# BloopPadMaxx_01.net
KiCad netlist of a schematic drawn in Altium Designer
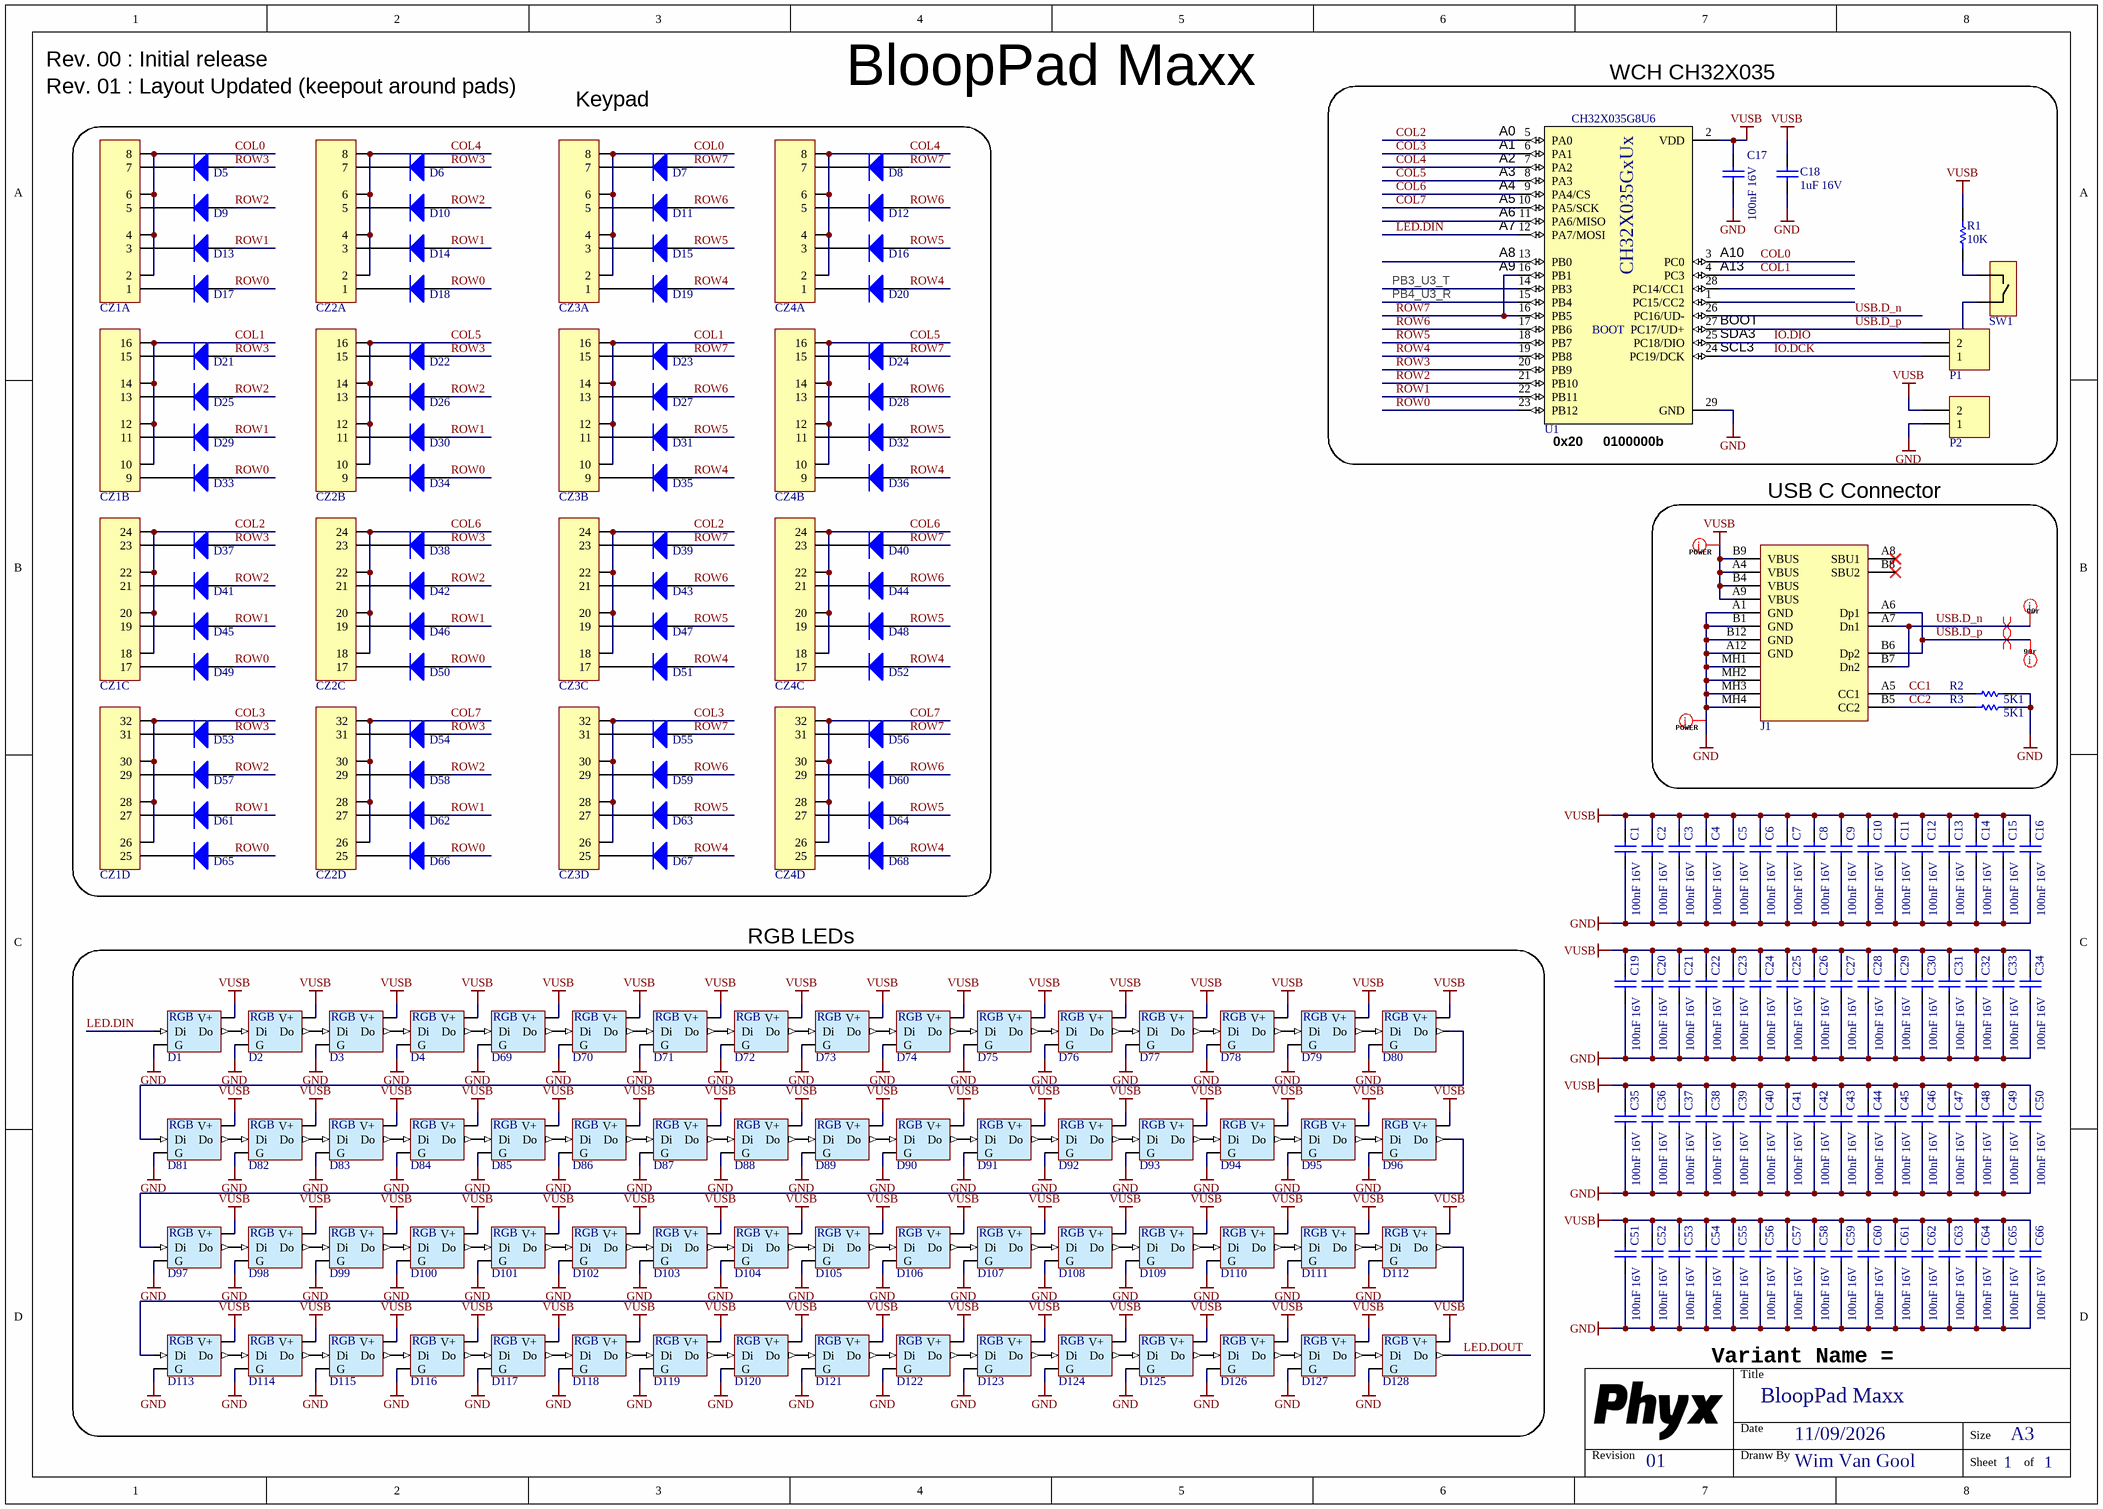
[diagram p0: BloopPadMaxx_01.SchDoc]

(export (version "E")
  (design (tool "Eeschema 10.0.6"))
  (components
    (comp (ref "C1")
      (value "100nF 16V")
      (footprint "C0603_N")
      (description "Capacitor Ceramic")
      (fields (field (name "Comment") "CAP_CERAMIC"))
      (libsource (lib "Phyx_Components") (part "CAP_CERAMIC"))
    )
    (comp (ref "C2")
      (value "100nF 16V")
      (footprint "C0603_N")
      (description "Capacitor Ceramic")
      (fields (field (name "Comment") "CAP_CERAMIC"))
      (libsource (lib "Phyx_Components") (part "CAP_CERAMIC"))
    )
    (comp (ref "C3")
      (value "100nF 16V")
      (footprint "C0603_N")
      (description "Capacitor Ceramic")
      (fields (field (name "Comment") "CAP_CERAMIC"))
      (libsource (lib "Phyx_Components") (part "CAP_CERAMIC"))
    )
    (comp (ref "C4")
      (value "100nF 16V")
      (footprint "C0603_N")
      (description "Capacitor Ceramic")
      (fields (field (name "Comment") "CAP_CERAMIC"))
      (libsource (lib "Phyx_Components") (part "CAP_CERAMIC"))
    )
    (comp (ref "C5")
      (value "100nF 16V")
      (footprint "C0603_N")
      (description "Capacitor Ceramic")
      (fields (field (name "Comment") "CAP_CERAMIC"))
      (libsource (lib "Phyx_Components") (part "CAP_CERAMIC"))
    )
    (comp (ref "C6")
      (value "100nF 16V")
      (footprint "C0603_N")
      (description "Capacitor Ceramic")
      (fields (field (name "Comment") "CAP_CERAMIC"))
      (libsource (lib "Phyx_Components") (part "CAP_CERAMIC"))
    )
    (comp (ref "C7")
      (value "100nF 16V")
      (footprint "C0603_N")
      (description "Capacitor Ceramic")
      (fields (field (name "Comment") "CAP_CERAMIC"))
      (libsource (lib "Phyx_Components") (part "CAP_CERAMIC"))
    )
    (comp (ref "C8")
      (value "100nF 16V")
      (footprint "C0603_N")
      (description "Capacitor Ceramic")
      (fields (field (name "Comment") "CAP_CERAMIC"))
      (libsource (lib "Phyx_Components") (part "CAP_CERAMIC"))
    )
    (comp (ref "C9")
      (value "100nF 16V")
      (footprint "C0603_N")
      (description "Capacitor Ceramic")
      (fields (field (name "Comment") "CAP_CERAMIC"))
      (libsource (lib "Phyx_Components") (part "CAP_CERAMIC"))
    )
    (comp (ref "C10")
      (value "100nF 16V")
      (footprint "C0603_N")
      (description "Capacitor Ceramic")
      (fields (field (name "Comment") "CAP_CERAMIC"))
      (libsource (lib "Phyx_Components") (part "CAP_CERAMIC"))
    )
    (comp (ref "C11")
      (value "100nF 16V")
      (footprint "C0603_N")
      (description "Capacitor Ceramic")
      (fields (field (name "Comment") "CAP_CERAMIC"))
      (libsource (lib "Phyx_Components") (part "CAP_CERAMIC"))
    )
    (comp (ref "C12")
      (value "100nF 16V")
      (footprint "C0603_N")
      (description "Capacitor Ceramic")
      (fields (field (name "Comment") "CAP_CERAMIC"))
      (libsource (lib "Phyx_Components") (part "CAP_CERAMIC"))
    )
    (comp (ref "C13")
      (value "100nF 16V")
      (footprint "C0603_N")
      (description "Capacitor Ceramic")
      (fields (field (name "Comment") "CAP_CERAMIC"))
      (libsource (lib "Phyx_Components") (part "CAP_CERAMIC"))
    )
    (comp (ref "C14")
      (value "100nF 16V")
      (footprint "C0603_N")
      (description "Capacitor Ceramic")
      (fields (field (name "Comment") "CAP_CERAMIC"))
      (libsource (lib "Phyx_Components") (part "CAP_CERAMIC"))
    )
    (comp (ref "C15")
      (value "100nF 16V")
      (footprint "C0603_N")
      (description "Capacitor Ceramic")
      (fields (field (name "Comment") "CAP_CERAMIC"))
      (libsource (lib "Phyx_Components") (part "CAP_CERAMIC"))
    )
    (comp (ref "C16")
      (value "100nF 16V")
      (footprint "C0603_N")
      (description "Capacitor Ceramic")
      (fields (field (name "Comment") "CAP_CERAMIC"))
      (libsource (lib "Phyx_Components") (part "CAP_CERAMIC"))
    )
    (comp (ref "C17")
      (value "100nF 16V")
      (footprint "C0603_N")
      (description "Capacitor Ceramic")
      (libsource (lib "Phyx_Components") (part "CAP_CERAMIC"))
    )
    (comp (ref "C18")
      (value "1uF 16V")
      (footprint "C0603_N")
      (description "Capacitor Ceramic")
      (libsource (lib "Phyx_Components") (part "CAP_CERAMIC"))
    )
    (comp (ref "C19")
      (value "100nF 16V")
      (footprint "C0603_N")
      (description "Capacitor Ceramic")
      (fields (field (name "Comment") "CAP_CERAMIC"))
      (libsource (lib "Phyx_Components") (part "CAP_CERAMIC"))
    )
    (comp (ref "C20")
      (value "100nF 16V")
      (footprint "C0603_N")
      (description "Capacitor Ceramic")
      (fields (field (name "Comment") "CAP_CERAMIC"))
      (libsource (lib "Phyx_Components") (part "CAP_CERAMIC"))
    )
    (comp (ref "C21")
      (value "100nF 16V")
      (footprint "C0603_N")
      (description "Capacitor Ceramic")
      (fields (field (name "Comment") "CAP_CERAMIC"))
      (libsource (lib "Phyx_Components") (part "CAP_CERAMIC"))
    )
    (comp (ref "C22")
      (value "100nF 16V")
      (footprint "C0603_N")
      (description "Capacitor Ceramic")
      (fields (field (name "Comment") "CAP_CERAMIC"))
      (libsource (lib "Phyx_Components") (part "CAP_CERAMIC"))
    )
    (comp (ref "C23")
      (value "100nF 16V")
      (footprint "C0603_N")
      (description "Capacitor Ceramic")
      (fields (field (name "Comment") "CAP_CERAMIC"))
      (libsource (lib "Phyx_Components") (part "CAP_CERAMIC"))
    )
    (comp (ref "C24")
      (value "100nF 16V")
      (footprint "C0603_N")
      (description "Capacitor Ceramic")
      (fields (field (name "Comment") "CAP_CERAMIC"))
      (libsource (lib "Phyx_Components") (part "CAP_CERAMIC"))
    )
    (comp (ref "C25")
      (value "100nF 16V")
      (footprint "C0603_N")
      (description "Capacitor Ceramic")
      (fields (field (name "Comment") "CAP_CERAMIC"))
      (libsource (lib "Phyx_Components") (part "CAP_CERAMIC"))
    )
    (comp (ref "C26")
      (value "100nF 16V")
      (footprint "C0603_N")
      (description "Capacitor Ceramic")
      (fields (field (name "Comment") "CAP_CERAMIC"))
      (libsource (lib "Phyx_Components") (part "CAP_CERAMIC"))
    )
    (comp (ref "C27")
      (value "100nF 16V")
      (footprint "C0603_N")
      (description "Capacitor Ceramic")
      (fields (field (name "Comment") "CAP_CERAMIC"))
      (libsource (lib "Phyx_Components") (part "CAP_CERAMIC"))
    )
    (comp (ref "C28")
      (value "100nF 16V")
      (footprint "C0603_N")
      (description "Capacitor Ceramic")
      (fields (field (name "Comment") "CAP_CERAMIC"))
      (libsource (lib "Phyx_Components") (part "CAP_CERAMIC"))
    )
    (comp (ref "C29")
      (value "100nF 16V")
      (footprint "C0603_N")
      (description "Capacitor Ceramic")
      (fields (field (name "Comment") "CAP_CERAMIC"))
      (libsource (lib "Phyx_Components") (part "CAP_CERAMIC"))
    )
    (comp (ref "C30")
      (value "100nF 16V")
      (footprint "C0603_N")
      (description "Capacitor Ceramic")
      (fields (field (name "Comment") "CAP_CERAMIC"))
      (libsource (lib "Phyx_Components") (part "CAP_CERAMIC"))
    )
    (comp (ref "C31")
      (value "100nF 16V")
      (footprint "C0603_N")
      (description "Capacitor Ceramic")
      (fields (field (name "Comment") "CAP_CERAMIC"))
      (libsource (lib "Phyx_Components") (part "CAP_CERAMIC"))
    )
    (comp (ref "C32")
      (value "100nF 16V")
      (footprint "C0603_N")
      (description "Capacitor Ceramic")
      (fields (field (name "Comment") "CAP_CERAMIC"))
      (libsource (lib "Phyx_Components") (part "CAP_CERAMIC"))
    )
    (comp (ref "C33")
      (value "100nF 16V")
      (footprint "C0603_N")
      (description "Capacitor Ceramic")
      (fields (field (name "Comment") "CAP_CERAMIC"))
      (libsource (lib "Phyx_Components") (part "CAP_CERAMIC"))
    )
    (comp (ref "C34")
      (value "100nF 16V")
      (footprint "C0603_N")
      (description "Capacitor Ceramic")
      (fields (field (name "Comment") "CAP_CERAMIC"))
      (libsource (lib "Phyx_Components") (part "CAP_CERAMIC"))
    )
    (comp (ref "C35")
      (value "100nF 16V")
      (footprint "C0603_N")
      (description "Capacitor Ceramic")
      (fields (field (name "Comment") "CAP_CERAMIC"))
      (libsource (lib "Phyx_Components") (part "CAP_CERAMIC"))
    )
    (comp (ref "C36")
      (value "100nF 16V")
      (footprint "C0603_N")
      (description "Capacitor Ceramic")
      (fields (field (name "Comment") "CAP_CERAMIC"))
      (libsource (lib "Phyx_Components") (part "CAP_CERAMIC"))
    )
    (comp (ref "C37")
      (value "100nF 16V")
      (footprint "C0603_N")
      (description "Capacitor Ceramic")
      (fields (field (name "Comment") "CAP_CERAMIC"))
      (libsource (lib "Phyx_Components") (part "CAP_CERAMIC"))
    )
    (comp (ref "C38")
      (value "100nF 16V")
      (footprint "C0603_N")
      (description "Capacitor Ceramic")
      (fields (field (name "Comment") "CAP_CERAMIC"))
      (libsource (lib "Phyx_Components") (part "CAP_CERAMIC"))
    )
    (comp (ref "C39")
      (value "100nF 16V")
      (footprint "C0603_N")
      (description "Capacitor Ceramic")
      (fields (field (name "Comment") "CAP_CERAMIC"))
      (libsource (lib "Phyx_Components") (part "CAP_CERAMIC"))
    )
    (comp (ref "C40")
      (value "100nF 16V")
      (footprint "C0603_N")
      (description "Capacitor Ceramic")
      (fields (field (name "Comment") "CAP_CERAMIC"))
      (libsource (lib "Phyx_Components") (part "CAP_CERAMIC"))
    )
    (comp (ref "C41")
      (value "100nF 16V")
      (footprint "C0603_N")
      (description "Capacitor Ceramic")
      (fields (field (name "Comment") "CAP_CERAMIC"))
      (libsource (lib "Phyx_Components") (part "CAP_CERAMIC"))
    )
    (comp (ref "C42")
      (value "100nF 16V")
      (footprint "C0603_N")
      (description "Capacitor Ceramic")
      (fields (field (name "Comment") "CAP_CERAMIC"))
      (libsource (lib "Phyx_Components") (part "CAP_CERAMIC"))
    )
    (comp (ref "C43")
      (value "100nF 16V")
      (footprint "C0603_N")
      (description "Capacitor Ceramic")
      (fields (field (name "Comment") "CAP_CERAMIC"))
      (libsource (lib "Phyx_Components") (part "CAP_CERAMIC"))
    )
    (comp (ref "C44")
      (value "100nF 16V")
      (footprint "C0603_N")
      (description "Capacitor Ceramic")
      (fields (field (name "Comment") "CAP_CERAMIC"))
      (libsource (lib "Phyx_Components") (part "CAP_CERAMIC"))
    )
    (comp (ref "C45")
      (value "100nF 16V")
      (footprint "C0603_N")
      (description "Capacitor Ceramic")
      (fields (field (name "Comment") "CAP_CERAMIC"))
      (libsource (lib "Phyx_Components") (part "CAP_CERAMIC"))
    )
    (comp (ref "C46")
      (value "100nF 16V")
      (footprint "C0603_N")
      (description "Capacitor Ceramic")
      (fields (field (name "Comment") "CAP_CERAMIC"))
      (libsource (lib "Phyx_Components") (part "CAP_CERAMIC"))
    )
    (comp (ref "C47")
      (value "100nF 16V")
      (footprint "C0603_N")
      (description "Capacitor Ceramic")
      (fields (field (name "Comment") "CAP_CERAMIC"))
      (libsource (lib "Phyx_Components") (part "CAP_CERAMIC"))
    )
    (comp (ref "C48")
      (value "100nF 16V")
      (footprint "C0603_N")
      (description "Capacitor Ceramic")
      (fields (field (name "Comment") "CAP_CERAMIC"))
      (libsource (lib "Phyx_Components") (part "CAP_CERAMIC"))
    )
    (comp (ref "C49")
      (value "100nF 16V")
      (footprint "C0603_N")
      (description "Capacitor Ceramic")
      (fields (field (name "Comment") "CAP_CERAMIC"))
      (libsource (lib "Phyx_Components") (part "CAP_CERAMIC"))
    )
    (comp (ref "C50")
      (value "100nF 16V")
      (footprint "C0603_N")
      (description "Capacitor Ceramic")
      (fields (field (name "Comment") "CAP_CERAMIC"))
      (libsource (lib "Phyx_Components") (part "CAP_CERAMIC"))
    )
    (comp (ref "C51")
      (value "100nF 16V")
      (footprint "C0603_N")
      (description "Capacitor Ceramic")
      (fields (field (name "Comment") "CAP_CERAMIC"))
      (libsource (lib "Phyx_Components") (part "CAP_CERAMIC"))
    )
    (comp (ref "C52")
      (value "100nF 16V")
      (footprint "C0603_N")
      (description "Capacitor Ceramic")
      (fields (field (name "Comment") "CAP_CERAMIC"))
      (libsource (lib "Phyx_Components") (part "CAP_CERAMIC"))
    )
    (comp (ref "C53")
      (value "100nF 16V")
      (footprint "C0603_N")
      (description "Capacitor Ceramic")
      (fields (field (name "Comment") "CAP_CERAMIC"))
      (libsource (lib "Phyx_Components") (part "CAP_CERAMIC"))
    )
    (comp (ref "C54")
      (value "100nF 16V")
      (footprint "C0603_N")
      (description "Capacitor Ceramic")
      (fields (field (name "Comment") "CAP_CERAMIC"))
      (libsource (lib "Phyx_Components") (part "CAP_CERAMIC"))
    )
    (comp (ref "C55")
      (value "100nF 16V")
      (footprint "C0603_N")
      (description "Capacitor Ceramic")
      (fields (field (name "Comment") "CAP_CERAMIC"))
      (libsource (lib "Phyx_Components") (part "CAP_CERAMIC"))
    )
    (comp (ref "C56")
      (value "100nF 16V")
      (footprint "C0603_N")
      (description "Capacitor Ceramic")
      (fields (field (name "Comment") "CAP_CERAMIC"))
      (libsource (lib "Phyx_Components") (part "CAP_CERAMIC"))
    )
    (comp (ref "C57")
      (value "100nF 16V")
      (footprint "C0603_N")
      (description "Capacitor Ceramic")
      (fields (field (name "Comment") "CAP_CERAMIC"))
      (libsource (lib "Phyx_Components") (part "CAP_CERAMIC"))
    )
    (comp (ref "C58")
      (value "100nF 16V")
      (footprint "C0603_N")
      (description "Capacitor Ceramic")
      (fields (field (name "Comment") "CAP_CERAMIC"))
      (libsource (lib "Phyx_Components") (part "CAP_CERAMIC"))
    )
    (comp (ref "C59")
      (value "100nF 16V")
      (footprint "C0603_N")
      (description "Capacitor Ceramic")
      (fields (field (name "Comment") "CAP_CERAMIC"))
      (libsource (lib "Phyx_Components") (part "CAP_CERAMIC"))
    )
    (comp (ref "C60")
      (value "100nF 16V")
      (footprint "C0603_N")
      (description "Capacitor Ceramic")
      (fields (field (name "Comment") "CAP_CERAMIC"))
      (libsource (lib "Phyx_Components") (part "CAP_CERAMIC"))
    )
    (comp (ref "C61")
      (value "100nF 16V")
      (footprint "C0603_N")
      (description "Capacitor Ceramic")
      (fields (field (name "Comment") "CAP_CERAMIC"))
      (libsource (lib "Phyx_Components") (part "CAP_CERAMIC"))
    )
    (comp (ref "C62")
      (value "100nF 16V")
      (footprint "C0603_N")
      (description "Capacitor Ceramic")
      (fields (field (name "Comment") "CAP_CERAMIC"))
      (libsource (lib "Phyx_Components") (part "CAP_CERAMIC"))
    )
    (comp (ref "C63")
      (value "100nF 16V")
      (footprint "C0603_N")
      (description "Capacitor Ceramic")
      (fields (field (name "Comment") "CAP_CERAMIC"))
      (libsource (lib "Phyx_Components") (part "CAP_CERAMIC"))
    )
    (comp (ref "C64")
      (value "100nF 16V")
      (footprint "C0603_N")
      (description "Capacitor Ceramic")
      (fields (field (name "Comment") "CAP_CERAMIC"))
      (libsource (lib "Phyx_Components") (part "CAP_CERAMIC"))
    )
    (comp (ref "C65")
      (value "100nF 16V")
      (footprint "C0603_N")
      (description "Capacitor Ceramic")
      (fields (field (name "Comment") "CAP_CERAMIC"))
      (libsource (lib "Phyx_Components") (part "CAP_CERAMIC"))
    )
    (comp (ref "C66")
      (value "100nF 16V")
      (footprint "C0603_N")
      (description "Capacitor Ceramic")
      (fields (field (name "Comment") "CAP_CERAMIC"))
      (libsource (lib "Phyx_Components") (part "CAP_CERAMIC"))
    )
    (comp (ref "CZ1")
      (value "Campzone 2020 4x4 silicone keypad")
      (footprint "CZ20_4x4")
      (libsource (lib "Phyx_Components") (part "CZ20_4x4"))
    )
    (comp (ref "CZ2")
      (value "Campzone 2020 4x4 silicone keypad")
      (footprint "CZ20_4x4")
      (libsource (lib "Phyx_Components") (part "CZ20_4x4"))
    )
    (comp (ref "CZ3")
      (value "Campzone 2020 4x4 silicone keypad")
      (footprint "CZ20_4x4")
      (libsource (lib "Phyx_Components") (part "CZ20_4x4"))
    )
    (comp (ref "CZ4")
      (value "Campzone 2020 4x4 silicone keypad")
      (footprint "CZ20_4x4")
      (libsource (lib "Phyx_Components") (part "CZ20_4x4"))
    )
    (comp (ref "D1")
      (value "WS2812 based digital RGB LED 2022 package")
      (footprint "LED_2022_WS2812B")
      (description "=Description")
      (libsource (lib "Phyx_Components") (part "LED_RGB_WS2812B_2022"))
    )
    (comp (ref "D2")
      (value "WS2812 based digital RGB LED 2022 package")
      (footprint "LED_2022_WS2812B")
      (description "=Description")
      (libsource (lib "Phyx_Components") (part "LED_RGB_WS2812B_2022"))
    )
    (comp (ref "D3")
      (value "WS2812 based digital RGB LED 2022 package")
      (footprint "LED_2022_WS2812B")
      (description "=Description")
      (libsource (lib "Phyx_Components") (part "LED_RGB_WS2812B_2022"))
    )
    (comp (ref "D4")
      (value "WS2812 based digital RGB LED 2022 package")
      (footprint "LED_2022_WS2812B")
      (description "=Description")
      (libsource (lib "Phyx_Components") (part "LED_RGB_WS2812B_2022"))
    )
    (comp (ref "D5")
      (value "1N4148W 75V 200mA 1.25Vf@150mA")
      (footprint "SOD-323_AC")
      (description "Default Diode")
      (libsource (lib "Phyx_Components") (part "DIODE_AC"))
    )
    (comp (ref "D6")
      (value "1N4148W 75V 200mA 1.25Vf@150mA")
      (footprint "SOD-323_AC")
      (description "Default Diode")
      (libsource (lib "Phyx_Components") (part "DIODE_AC"))
    )
    (comp (ref "D7")
      (value "1N4148W 75V 200mA 1.25Vf@150mA")
      (footprint "SOD-323_AC")
      (description "Default Diode")
      (libsource (lib "Phyx_Components") (part "DIODE_AC"))
    )
    (comp (ref "D8")
      (value "1N4148W 75V 200mA 1.25Vf@150mA")
      (footprint "SOD-323_AC")
      (description "Default Diode")
      (libsource (lib "Phyx_Components") (part "DIODE_AC"))
    )
    (comp (ref "D9")
      (value "1N4148W 75V 200mA 1.25Vf@150mA")
      (footprint "SOD-323_AC")
      (description "Default Diode")
      (libsource (lib "Phyx_Components") (part "DIODE_AC"))
    )
    (comp (ref "D10")
      (value "1N4148W 75V 200mA 1.25Vf@150mA")
      (footprint "SOD-323_AC")
      (description "Default Diode")
      (libsource (lib "Phyx_Components") (part "DIODE_AC"))
    )
    (comp (ref "D11")
      (value "1N4148W 75V 200mA 1.25Vf@150mA")
      (footprint "SOD-323_AC")
      (description "Default Diode")
      (libsource (lib "Phyx_Components") (part "DIODE_AC"))
    )
    (comp (ref "D12")
      (value "1N4148W 75V 200mA 1.25Vf@150mA")
      (footprint "SOD-323_AC")
      (description "Default Diode")
      (libsource (lib "Phyx_Components") (part "DIODE_AC"))
    )
    (comp (ref "D13")
      (value "1N4148W 75V 200mA 1.25Vf@150mA")
      (footprint "SOD-323_AC")
      (description "Default Diode")
      (libsource (lib "Phyx_Components") (part "DIODE_AC"))
    )
    (comp (ref "D14")
      (value "1N4148W 75V 200mA 1.25Vf@150mA")
      (footprint "SOD-323_AC")
      (description "Default Diode")
      (libsource (lib "Phyx_Components") (part "DIODE_AC"))
    )
    (comp (ref "D15")
      (value "1N4148W 75V 200mA 1.25Vf@150mA")
      (footprint "SOD-323_AC")
      (description "Default Diode")
      (libsource (lib "Phyx_Components") (part "DIODE_AC"))
    )
    (comp (ref "D16")
      (value "1N4148W 75V 200mA 1.25Vf@150mA")
      (footprint "SOD-323_AC")
      (description "Default Diode")
      (libsource (lib "Phyx_Components") (part "DIODE_AC"))
    )
    (comp (ref "D17")
      (value "1N4148W 75V 200mA 1.25Vf@150mA")
      (footprint "SOD-323_AC")
      (description "Default Diode")
      (libsource (lib "Phyx_Components") (part "DIODE_AC"))
    )
    (comp (ref "D18")
      (value "1N4148W 75V 200mA 1.25Vf@150mA")
      (footprint "SOD-323_AC")
      (description "Default Diode")
      (libsource (lib "Phyx_Components") (part "DIODE_AC"))
    )
    (comp (ref "D19")
      (value "1N4148W 75V 200mA 1.25Vf@150mA")
      (footprint "SOD-323_AC")
      (description "Default Diode")
      (libsource (lib "Phyx_Components") (part "DIODE_AC"))
    )
    (comp (ref "D20")
      (value "1N4148W 75V 200mA 1.25Vf@150mA")
      (footprint "SOD-323_AC")
      (description "Default Diode")
      (libsource (lib "Phyx_Components") (part "DIODE_AC"))
    )
    (comp (ref "D21")
      (value "1N4148W 75V 200mA 1.25Vf@150mA")
      (footprint "SOD-323_AC")
      (description "Default Diode")
      (libsource (lib "Phyx_Components") (part "DIODE_AC"))
    )
    (comp (ref "D22")
      (value "1N4148W 75V 200mA 1.25Vf@150mA")
      (footprint "SOD-323_AC")
      (description "Default Diode")
      (libsource (lib "Phyx_Components") (part "DIODE_AC"))
    )
    (comp (ref "D23")
      (value "1N4148W 75V 200mA 1.25Vf@150mA")
      (footprint "SOD-323_AC")
      (description "Default Diode")
      (libsource (lib "Phyx_Components") (part "DIODE_AC"))
    )
    (comp (ref "D24")
      (value "1N4148W 75V 200mA 1.25Vf@150mA")
      (footprint "SOD-323_AC")
      (description "Default Diode")
      (libsource (lib "Phyx_Components") (part "DIODE_AC"))
    )
    (comp (ref "D25")
      (value "1N4148W 75V 200mA 1.25Vf@150mA")
      (footprint "SOD-323_AC")
      (description "Default Diode")
      (libsource (lib "Phyx_Components") (part "DIODE_AC"))
    )
    (comp (ref "D26")
      (value "1N4148W 75V 200mA 1.25Vf@150mA")
      (footprint "SOD-323_AC")
      (description "Default Diode")
      (libsource (lib "Phyx_Components") (part "DIODE_AC"))
    )
    (comp (ref "D27")
      (value "1N4148W 75V 200mA 1.25Vf@150mA")
      (footprint "SOD-323_AC")
      (description "Default Diode")
      (libsource (lib "Phyx_Components") (part "DIODE_AC"))
    )
    (comp (ref "D28")
      (value "1N4148W 75V 200mA 1.25Vf@150mA")
      (footprint "SOD-323_AC")
      (description "Default Diode")
      (libsource (lib "Phyx_Components") (part "DIODE_AC"))
    )
    (comp (ref "D29")
      (value "1N4148W 75V 200mA 1.25Vf@150mA")
      (footprint "SOD-323_AC")
      (description "Default Diode")
      (libsource (lib "Phyx_Components") (part "DIODE_AC"))
    )
    (comp (ref "D30")
      (value "1N4148W 75V 200mA 1.25Vf@150mA")
      (footprint "SOD-323_AC")
      (description "Default Diode")
      (libsource (lib "Phyx_Components") (part "DIODE_AC"))
    )
    (comp (ref "D31")
      (value "1N4148W 75V 200mA 1.25Vf@150mA")
      (footprint "SOD-323_AC")
      (description "Default Diode")
      (libsource (lib "Phyx_Components") (part "DIODE_AC"))
    )
    (comp (ref "D32")
      (value "1N4148W 75V 200mA 1.25Vf@150mA")
      (footprint "SOD-323_AC")
      (description "Default Diode")
      (libsource (lib "Phyx_Components") (part "DIODE_AC"))
    )
    (comp (ref "D33")
      (value "1N4148W 75V 200mA 1.25Vf@150mA")
      (footprint "SOD-323_AC")
      (description "Default Diode")
      (libsource (lib "Phyx_Components") (part "DIODE_AC"))
    )
    (comp (ref "D34")
      (value "1N4148W 75V 200mA 1.25Vf@150mA")
      (footprint "SOD-323_AC")
      (description "Default Diode")
      (libsource (lib "Phyx_Components") (part "DIODE_AC"))
    )
    (comp (ref "D35")
      (value "1N4148W 75V 200mA 1.25Vf@150mA")
      (footprint "SOD-323_AC")
      (description "Default Diode")
      (libsource (lib "Phyx_Components") (part "DIODE_AC"))
    )
    (comp (ref "D36")
      (value "1N4148W 75V 200mA 1.25Vf@150mA")
      (footprint "SOD-323_AC")
      (description "Default Diode")
      (libsource (lib "Phyx_Components") (part "DIODE_AC"))
    )
    (comp (ref "D37")
      (value "1N4148W 75V 200mA 1.25Vf@150mA")
      (footprint "SOD-323_AC")
      (description "Default Diode")
      (libsource (lib "Phyx_Components") (part "DIODE_AC"))
    )
    (comp (ref "D38")
      (value "1N4148W 75V 200mA 1.25Vf@150mA")
      (footprint "SOD-323_AC")
      (description "Default Diode")
      (libsource (lib "Phyx_Components") (part "DIODE_AC"))
    )
    (comp (ref "D39")
      (value "1N4148W 75V 200mA 1.25Vf@150mA")
      (footprint "SOD-323_AC")
      (description "Default Diode")
      (libsource (lib "Phyx_Components") (part "DIODE_AC"))
    )
    (comp (ref "D40")
      (value "1N4148W 75V 200mA 1.25Vf@150mA")
      (footprint "SOD-323_AC")
      (description "Default Diode")
      (libsource (lib "Phyx_Components") (part "DIODE_AC"))
    )
    (comp (ref "D41")
      (value "1N4148W 75V 200mA 1.25Vf@150mA")
      (footprint "SOD-323_AC")
      (description "Default Diode")
      (libsource (lib "Phyx_Components") (part "DIODE_AC"))
    )
    (comp (ref "D42")
      (value "1N4148W 75V 200mA 1.25Vf@150mA")
      (footprint "SOD-323_AC")
      (description "Default Diode")
      (libsource (lib "Phyx_Components") (part "DIODE_AC"))
    )
    (comp (ref "D43")
      (value "1N4148W 75V 200mA 1.25Vf@150mA")
      (footprint "SOD-323_AC")
      (description "Default Diode")
      (libsource (lib "Phyx_Components") (part "DIODE_AC"))
    )
    (comp (ref "D44")
      (value "1N4148W 75V 200mA 1.25Vf@150mA")
      (footprint "SOD-323_AC")
      (description "Default Diode")
      (libsource (lib "Phyx_Components") (part "DIODE_AC"))
    )
    (comp (ref "D45")
      (value "1N4148W 75V 200mA 1.25Vf@150mA")
      (footprint "SOD-323_AC")
      (description "Default Diode")
      (libsource (lib "Phyx_Components") (part "DIODE_AC"))
    )
    (comp (ref "D46")
      (value "1N4148W 75V 200mA 1.25Vf@150mA")
      (footprint "SOD-323_AC")
      (description "Default Diode")
      (libsource (lib "Phyx_Components") (part "DIODE_AC"))
    )
    (comp (ref "D47")
      (value "1N4148W 75V 200mA 1.25Vf@150mA")
      (footprint "SOD-323_AC")
      (description "Default Diode")
      (libsource (lib "Phyx_Components") (part "DIODE_AC"))
    )
    (comp (ref "D48")
      (value "1N4148W 75V 200mA 1.25Vf@150mA")
      (footprint "SOD-323_AC")
      (description "Default Diode")
      (libsource (lib "Phyx_Components") (part "DIODE_AC"))
    )
    (comp (ref "D49")
      (value "1N4148W 75V 200mA 1.25Vf@150mA")
      (footprint "SOD-323_AC")
      (description "Default Diode")
      (libsource (lib "Phyx_Components") (part "DIODE_AC"))
    )
    (comp (ref "D50")
      (value "1N4148W 75V 200mA 1.25Vf@150mA")
      (footprint "SOD-323_AC")
      (description "Default Diode")
      (libsource (lib "Phyx_Components") (part "DIODE_AC"))
    )
    (comp (ref "D51")
      (value "1N4148W 75V 200mA 1.25Vf@150mA")
      (footprint "SOD-323_AC")
      (description "Default Diode")
      (libsource (lib "Phyx_Components") (part "DIODE_AC"))
    )
    (comp (ref "D52")
      (value "1N4148W 75V 200mA 1.25Vf@150mA")
      (footprint "SOD-323_AC")
      (description "Default Diode")
      (libsource (lib "Phyx_Components") (part "DIODE_AC"))
    )
    (comp (ref "D53")
      (value "1N4148W 75V 200mA 1.25Vf@150mA")
      (footprint "SOD-323_AC")
      (description "Default Diode")
      (libsource (lib "Phyx_Components") (part "DIODE_AC"))
    )
    (comp (ref "D54")
      (value "1N4148W 75V 200mA 1.25Vf@150mA")
      (footprint "SOD-323_AC")
      (description "Default Diode")
      (libsource (lib "Phyx_Components") (part "DIODE_AC"))
    )
    (comp (ref "D55")
      (value "1N4148W 75V 200mA 1.25Vf@150mA")
      (footprint "SOD-323_AC")
      (description "Default Diode")
      (libsource (lib "Phyx_Components") (part "DIODE_AC"))
    )
    (comp (ref "D56")
      (value "1N4148W 75V 200mA 1.25Vf@150mA")
      (footprint "SOD-323_AC")
      (description "Default Diode")
      (libsource (lib "Phyx_Components") (part "DIODE_AC"))
    )
    (comp (ref "D57")
      (value "1N4148W 75V 200mA 1.25Vf@150mA")
      (footprint "SOD-323_AC")
      (description "Default Diode")
      (libsource (lib "Phyx_Components") (part "DIODE_AC"))
    )
    (comp (ref "D58")
      (value "1N4148W 75V 200mA 1.25Vf@150mA")
      (footprint "SOD-323_AC")
      (description "Default Diode")
      (libsource (lib "Phyx_Components") (part "DIODE_AC"))
    )
    (comp (ref "D59")
      (value "1N4148W 75V 200mA 1.25Vf@150mA")
      (footprint "SOD-323_AC")
      (description "Default Diode")
      (libsource (lib "Phyx_Components") (part "DIODE_AC"))
    )
    (comp (ref "D60")
      (value "1N4148W 75V 200mA 1.25Vf@150mA")
      (footprint "SOD-323_AC")
      (description "Default Diode")
      (libsource (lib "Phyx_Components") (part "DIODE_AC"))
    )
    (comp (ref "D61")
      (value "1N4148W 75V 200mA 1.25Vf@150mA")
      (footprint "SOD-323_AC")
      (description "Default Diode")
      (libsource (lib "Phyx_Components") (part "DIODE_AC"))
    )
    (comp (ref "D62")
      (value "1N4148W 75V 200mA 1.25Vf@150mA")
      (footprint "SOD-323_AC")
      (description "Default Diode")
      (libsource (lib "Phyx_Components") (part "DIODE_AC"))
    )
    (comp (ref "D63")
      (value "1N4148W 75V 200mA 1.25Vf@150mA")
      (footprint "SOD-323_AC")
      (description "Default Diode")
      (libsource (lib "Phyx_Components") (part "DIODE_AC"))
    )
    (comp (ref "D64")
      (value "1N4148W 75V 200mA 1.25Vf@150mA")
      (footprint "SOD-323_AC")
      (description "Default Diode")
      (libsource (lib "Phyx_Components") (part "DIODE_AC"))
    )
    (comp (ref "D65")
      (value "1N4148W 75V 200mA 1.25Vf@150mA")
      (footprint "SOD-323_AC")
      (description "Default Diode")
      (libsource (lib "Phyx_Components") (part "DIODE_AC"))
    )
    (comp (ref "D66")
      (value "1N4148W 75V 200mA 1.25Vf@150mA")
      (footprint "SOD-323_AC")
      (description "Default Diode")
      (libsource (lib "Phyx_Components") (part "DIODE_AC"))
    )
    (comp (ref "D67")
      (value "1N4148W 75V 200mA 1.25Vf@150mA")
      (footprint "SOD-323_AC")
      (description "Default Diode")
      (libsource (lib "Phyx_Components") (part "DIODE_AC"))
    )
    (comp (ref "D68")
      (value "1N4148W 75V 200mA 1.25Vf@150mA")
      (footprint "SOD-323_AC")
      (description "Default Diode")
      (libsource (lib "Phyx_Components") (part "DIODE_AC"))
    )
    (comp (ref "D69")
      (value "WS2812 based digital RGB LED 2022 package")
      (footprint "LED_2022_WS2812B")
      (description "=Description")
      (libsource (lib "Phyx_Components") (part "LED_RGB_WS2812B_2022"))
    )
    (comp (ref "D70")
      (value "WS2812 based digital RGB LED 2022 package")
      (footprint "LED_2022_WS2812B")
      (description "=Description")
      (libsource (lib "Phyx_Components") (part "LED_RGB_WS2812B_2022"))
    )
    (comp (ref "D71")
      (value "WS2812 based digital RGB LED 2022 package")
      (footprint "LED_2022_WS2812B")
      (description "=Description")
      (libsource (lib "Phyx_Components") (part "LED_RGB_WS2812B_2022"))
    )
    (comp (ref "D72")
      (value "WS2812 based digital RGB LED 2022 package")
      (footprint "LED_2022_WS2812B")
      (description "=Description")
      (libsource (lib "Phyx_Components") (part "LED_RGB_WS2812B_2022"))
    )
    (comp (ref "D73")
      (value "WS2812 based digital RGB LED 2022 package")
      (footprint "LED_2022_WS2812B")
      (description "=Description")
      (libsource (lib "Phyx_Components") (part "LED_RGB_WS2812B_2022"))
    )
    (comp (ref "D74")
      (value "WS2812 based digital RGB LED 2022 package")
      (footprint "LED_2022_WS2812B")
      (description "=Description")
      (libsource (lib "Phyx_Components") (part "LED_RGB_WS2812B_2022"))
    )
    (comp (ref "D75")
      (value "WS2812 based digital RGB LED 2022 package")
      (footprint "LED_2022_WS2812B")
      (description "=Description")
      (libsource (lib "Phyx_Components") (part "LED_RGB_WS2812B_2022"))
    )
    (comp (ref "D76")
      (value "WS2812 based digital RGB LED 2022 package")
      (footprint "LED_2022_WS2812B")
      (description "=Description")
      (libsource (lib "Phyx_Components") (part "LED_RGB_WS2812B_2022"))
    )
    (comp (ref "D77")
      (value "WS2812 based digital RGB LED 2022 package")
      (footprint "LED_2022_WS2812B")
      (description "=Description")
      (libsource (lib "Phyx_Components") (part "LED_RGB_WS2812B_2022"))
    )
    (comp (ref "D78")
      (value "WS2812 based digital RGB LED 2022 package")
      (footprint "LED_2022_WS2812B")
      (description "=Description")
      (libsource (lib "Phyx_Components") (part "LED_RGB_WS2812B_2022"))
    )
    (comp (ref "D79")
      (value "WS2812 based digital RGB LED 2022 package")
      (footprint "LED_2022_WS2812B")
      (description "=Description")
      (libsource (lib "Phyx_Components") (part "LED_RGB_WS2812B_2022"))
    )
    (comp (ref "D80")
      (value "WS2812 based digital RGB LED 2022 package")
      (footprint "LED_2022_WS2812B")
      (description "=Description")
      (libsource (lib "Phyx_Components") (part "LED_RGB_WS2812B_2022"))
    )
    (comp (ref "D81")
      (value "WS2812 based digital RGB LED 2022 package")
      (footprint "LED_2022_WS2812B")
      (description "=Description")
      (libsource (lib "Phyx_Components") (part "LED_RGB_WS2812B_2022"))
    )
    (comp (ref "D82")
      (value "WS2812 based digital RGB LED 2022 package")
      (footprint "LED_2022_WS2812B")
      (description "=Description")
      (libsource (lib "Phyx_Components") (part "LED_RGB_WS2812B_2022"))
    )
    (comp (ref "D83")
      (value "WS2812 based digital RGB LED 2022 package")
      (footprint "LED_2022_WS2812B")
      (description "=Description")
      (libsource (lib "Phyx_Components") (part "LED_RGB_WS2812B_2022"))
    )
    (comp (ref "D84")
      (value "WS2812 based digital RGB LED 2022 package")
      (footprint "LED_2022_WS2812B")
      (description "=Description")
      (libsource (lib "Phyx_Components") (part "LED_RGB_WS2812B_2022"))
    )
    (comp (ref "D85")
      (value "WS2812 based digital RGB LED 2022 package")
      (footprint "LED_2022_WS2812B")
      (description "=Description")
      (libsource (lib "Phyx_Components") (part "LED_RGB_WS2812B_2022"))
    )
    (comp (ref "D86")
      (value "WS2812 based digital RGB LED 2022 package")
      (footprint "LED_2022_WS2812B")
      (description "=Description")
      (libsource (lib "Phyx_Components") (part "LED_RGB_WS2812B_2022"))
    )
    (comp (ref "D87")
      (value "WS2812 based digital RGB LED 2022 package")
      (footprint "LED_2022_WS2812B")
      (description "=Description")
      (libsource (lib "Phyx_Components") (part "LED_RGB_WS2812B_2022"))
    )
    (comp (ref "D88")
      (value "WS2812 based digital RGB LED 2022 package")
      (footprint "LED_2022_WS2812B")
      (description "=Description")
      (libsource (lib "Phyx_Components") (part "LED_RGB_WS2812B_2022"))
    )
    (comp (ref "D89")
      (value "WS2812 based digital RGB LED 2022 package")
      (footprint "LED_2022_WS2812B")
      (description "=Description")
      (libsource (lib "Phyx_Components") (part "LED_RGB_WS2812B_2022"))
    )
    (comp (ref "D90")
      (value "WS2812 based digital RGB LED 2022 package")
      (footprint "LED_2022_WS2812B")
      (description "=Description")
      (libsource (lib "Phyx_Components") (part "LED_RGB_WS2812B_2022"))
    )
    (comp (ref "D91")
      (value "WS2812 based digital RGB LED 2022 package")
      (footprint "LED_2022_WS2812B")
      (description "=Description")
      (libsource (lib "Phyx_Components") (part "LED_RGB_WS2812B_2022"))
    )
    (comp (ref "D92")
      (value "WS2812 based digital RGB LED 2022 package")
      (footprint "LED_2022_WS2812B")
      (description "=Description")
      (libsource (lib "Phyx_Components") (part "LED_RGB_WS2812B_2022"))
    )
    (comp (ref "D93")
      (value "WS2812 based digital RGB LED 2022 package")
      (footprint "LED_2022_WS2812B")
      (description "=Description")
      (libsource (lib "Phyx_Components") (part "LED_RGB_WS2812B_2022"))
    )
    (comp (ref "D94")
      (value "WS2812 based digital RGB LED 2022 package")
      (footprint "LED_2022_WS2812B")
      (description "=Description")
      (libsource (lib "Phyx_Components") (part "LED_RGB_WS2812B_2022"))
    )
    (comp (ref "D95")
      (value "WS2812 based digital RGB LED 2022 package")
      (footprint "LED_2022_WS2812B")
      (description "=Description")
      (libsource (lib "Phyx_Components") (part "LED_RGB_WS2812B_2022"))
    )
    (comp (ref "D96")
      (value "WS2812 based digital RGB LED 2022 package")
      (footprint "LED_2022_WS2812B")
      (description "=Description")
      (libsource (lib "Phyx_Components") (part "LED_RGB_WS2812B_2022"))
    )
    (comp (ref "D97")
      (value "WS2812 based digital RGB LED 2022 package")
      (footprint "LED_2022_WS2812B")
      (description "=Description")
      (libsource (lib "Phyx_Components") (part "LED_RGB_WS2812B_2022"))
    )
    (comp (ref "D98")
      (value "WS2812 based digital RGB LED 2022 package")
      (footprint "LED_2022_WS2812B")
      (description "=Description")
      (libsource (lib "Phyx_Components") (part "LED_RGB_WS2812B_2022"))
    )
    (comp (ref "D99")
      (value "WS2812 based digital RGB LED 2022 package")
      (footprint "LED_2022_WS2812B")
      (description "=Description")
      (libsource (lib "Phyx_Components") (part "LED_RGB_WS2812B_2022"))
    )
    (comp (ref "D100")
      (value "WS2812 based digital RGB LED 2022 package")
      (footprint "LED_2022_WS2812B")
      (description "=Description")
      (libsource (lib "Phyx_Components") (part "LED_RGB_WS2812B_2022"))
    )
    (comp (ref "D101")
      (value "WS2812 based digital RGB LED 2022 package")
      (footprint "LED_2022_WS2812B")
      (description "=Description")
      (libsource (lib "Phyx_Components") (part "LED_RGB_WS2812B_2022"))
    )
    (comp (ref "D102")
      (value "WS2812 based digital RGB LED 2022 package")
      (footprint "LED_2022_WS2812B")
      (description "=Description")
      (libsource (lib "Phyx_Components") (part "LED_RGB_WS2812B_2022"))
    )
    (comp (ref "D103")
      (value "WS2812 based digital RGB LED 2022 package")
      (footprint "LED_2022_WS2812B")
      (description "=Description")
      (libsource (lib "Phyx_Components") (part "LED_RGB_WS2812B_2022"))
    )
    (comp (ref "D104")
      (value "WS2812 based digital RGB LED 2022 package")
      (footprint "LED_2022_WS2812B")
      (description "=Description")
      (libsource (lib "Phyx_Components") (part "LED_RGB_WS2812B_2022"))
    )
    (comp (ref "D105")
      (value "WS2812 based digital RGB LED 2022 package")
      (footprint "LED_2022_WS2812B")
      (description "=Description")
      (libsource (lib "Phyx_Components") (part "LED_RGB_WS2812B_2022"))
    )
    (comp (ref "D106")
      (value "WS2812 based digital RGB LED 2022 package")
      (footprint "LED_2022_WS2812B")
      (description "=Description")
      (libsource (lib "Phyx_Components") (part "LED_RGB_WS2812B_2022"))
    )
    (comp (ref "D107")
      (value "WS2812 based digital RGB LED 2022 package")
      (footprint "LED_2022_WS2812B")
      (description "=Description")
      (libsource (lib "Phyx_Components") (part "LED_RGB_WS2812B_2022"))
    )
    (comp (ref "D108")
      (value "WS2812 based digital RGB LED 2022 package")
      (footprint "LED_2022_WS2812B")
      (description "=Description")
      (libsource (lib "Phyx_Components") (part "LED_RGB_WS2812B_2022"))
    )
    (comp (ref "D109")
      (value "WS2812 based digital RGB LED 2022 package")
      (footprint "LED_2022_WS2812B")
      (description "=Description")
      (libsource (lib "Phyx_Components") (part "LED_RGB_WS2812B_2022"))
    )
    (comp (ref "D110")
      (value "WS2812 based digital RGB LED 2022 package")
      (footprint "LED_2022_WS2812B")
      (description "=Description")
      (libsource (lib "Phyx_Components") (part "LED_RGB_WS2812B_2022"))
    )
    (comp (ref "D111")
      (value "WS2812 based digital RGB LED 2022 package")
      (footprint "LED_2022_WS2812B")
      (description "=Description")
      (libsource (lib "Phyx_Components") (part "LED_RGB_WS2812B_2022"))
    )
    (comp (ref "D112")
      (value "WS2812 based digital RGB LED 2022 package")
      (footprint "LED_2022_WS2812B")
      (description "=Description")
      (libsource (lib "Phyx_Components") (part "LED_RGB_WS2812B_2022"))
    )
    (comp (ref "D113")
      (value "WS2812 based digital RGB LED 2022 package")
      (footprint "LED_2022_WS2812B")
      (description "=Description")
      (libsource (lib "Phyx_Components") (part "LED_RGB_WS2812B_2022"))
    )
    (comp (ref "D114")
      (value "WS2812 based digital RGB LED 2022 package")
      (footprint "LED_2022_WS2812B")
      (description "=Description")
      (libsource (lib "Phyx_Components") (part "LED_RGB_WS2812B_2022"))
    )
    (comp (ref "D115")
      (value "WS2812 based digital RGB LED 2022 package")
      (footprint "LED_2022_WS2812B")
      (description "=Description")
      (libsource (lib "Phyx_Components") (part "LED_RGB_WS2812B_2022"))
    )
    (comp (ref "D116")
      (value "WS2812 based digital RGB LED 2022 package")
      (footprint "LED_2022_WS2812B")
      (description "=Description")
      (libsource (lib "Phyx_Components") (part "LED_RGB_WS2812B_2022"))
    )
    (comp (ref "D117")
      (value "WS2812 based digital RGB LED 2022 package")
      (footprint "LED_2022_WS2812B")
      (description "=Description")
      (libsource (lib "Phyx_Components") (part "LED_RGB_WS2812B_2022"))
    )
    (comp (ref "D118")
      (value "WS2812 based digital RGB LED 2022 package")
      (footprint "LED_2022_WS2812B")
      (description "=Description")
      (libsource (lib "Phyx_Components") (part "LED_RGB_WS2812B_2022"))
    )
    (comp (ref "D119")
      (value "WS2812 based digital RGB LED 2022 package")
      (footprint "LED_2022_WS2812B")
      (description "=Description")
      (libsource (lib "Phyx_Components") (part "LED_RGB_WS2812B_2022"))
    )
    (comp (ref "D120")
      (value "WS2812 based digital RGB LED 2022 package")
      (footprint "LED_2022_WS2812B")
      (description "=Description")
      (libsource (lib "Phyx_Components") (part "LED_RGB_WS2812B_2022"))
    )
    (comp (ref "D121")
      (value "WS2812 based digital RGB LED 2022 package")
      (footprint "LED_2022_WS2812B")
      (description "=Description")
      (libsource (lib "Phyx_Components") (part "LED_RGB_WS2812B_2022"))
    )
    (comp (ref "D122")
      (value "WS2812 based digital RGB LED 2022 package")
      (footprint "LED_2022_WS2812B")
      (description "=Description")
      (libsource (lib "Phyx_Components") (part "LED_RGB_WS2812B_2022"))
    )
    (comp (ref "D123")
      (value "WS2812 based digital RGB LED 2022 package")
      (footprint "LED_2022_WS2812B")
      (description "=Description")
      (libsource (lib "Phyx_Components") (part "LED_RGB_WS2812B_2022"))
    )
    (comp (ref "D124")
      (value "WS2812 based digital RGB LED 2022 package")
      (footprint "LED_2022_WS2812B")
      (description "=Description")
      (libsource (lib "Phyx_Components") (part "LED_RGB_WS2812B_2022"))
    )
    (comp (ref "D125")
      (value "WS2812 based digital RGB LED 2022 package")
      (footprint "LED_2022_WS2812B")
      (description "=Description")
      (libsource (lib "Phyx_Components") (part "LED_RGB_WS2812B_2022"))
    )
    (comp (ref "D126")
      (value "WS2812 based digital RGB LED 2022 package")
      (footprint "LED_2022_WS2812B")
      (description "=Description")
      (libsource (lib "Phyx_Components") (part "LED_RGB_WS2812B_2022"))
    )
    (comp (ref "D127")
      (value "WS2812 based digital RGB LED 2022 package")
      (footprint "LED_2022_WS2812B")
      (description "=Description")
      (libsource (lib "Phyx_Components") (part "LED_RGB_WS2812B_2022"))
    )
    (comp (ref "D128")
      (value "WS2812 based digital RGB LED 2022 package")
      (footprint "LED_2022_WS2812B")
      (description "=Description")
      (libsource (lib "Phyx_Components") (part "LED_RGB_WS2812B_2022"))
    )
    (comp (ref "J1")
      (value "USB 2.0 C Reversible Receptacle Horizontal full SMD")
      (footprint "XUNPU-TYPEC-304S-ACP16")
      (libsource (lib "Phyx_Components") (part "USB_C_16_4"))
    )
    (comp (ref "P1")
      (value "Header 2")
      (footprint "HDR1X2")
      (libsource (lib "Phyx_Components") (part "Header 2"))
    )
    (comp (ref "P2")
      (value "Header 2")
      (footprint "HDR1X2")
      (libsource (lib "Phyx_Components") (part "Header 2"))
    )
    (comp (ref "R1")
      (value "10K")
      (footprint "R0603_N")
      (libsource (lib "Phyx_Components") (part "RESISTOR"))
    )
    (comp (ref "R2")
      (value "5K1")
      (footprint "R0603_N")
      (libsource (lib "Phyx_Components") (part "RESISTOR"))
    )
    (comp (ref "R3")
      (value "5K1")
      (footprint "R0603_N")
      (libsource (lib "Phyx_Components") (part "RESISTOR"))
    )
    (comp (ref "SW1")
      (value "LP SMD tact sw 3x2.5mm")
      (footprint "OMR_B3U-1000P")
      (libsource (lib "Phyx_Components") (part "SW_TACT"))
    )
    (comp (ref "U1")
      (value "CH32X035G8U6")
      (footprint "QFN_28_4.0x4.0_P0.4")
      (fields
        (field (name "Comment") "WCH CH32X035G8U6 QFN28 RISC-V 32-bit MCU, 62KB Flash, 10KB RAM, USB PD")
      )
      (libsource (lib "Phyx_Components") (part "WCH_CH32X035GxUx"))
    )
  )
  (nets
    (net (code "1") (name "/CC1") (class "Default")
      (node (ref "J1") (pin "A5") (pinfunction "CC1_A5") (pintype "passive"))
      (node (ref "R2") (pin "1") (pinfunction "1_1") (pintype "passive"))
    )
    (net (code "2") (name "/CC2") (class "Default")
      (node (ref "J1") (pin "B5") (pinfunction "CC2_B5") (pintype "passive"))
      (node (ref "R3") (pin "1") (pinfunction "1_1") (pintype "passive"))
    )
    (net (code "3") (name "/COL0") (class "Default")
      (node (ref "CZ1") (pin "2") (pinfunction "2_2") (pintype "passive"))
      (node (ref "CZ1") (pin "4") (pinfunction "4_4") (pintype "passive"))
      (node (ref "CZ1") (pin "6") (pinfunction "6_6") (pintype "passive"))
      (node (ref "CZ1") (pin "8") (pinfunction "8_8") (pintype "passive"))
      (node (ref "CZ3") (pin "2") (pinfunction "2_2") (pintype "passive"))
      (node (ref "CZ3") (pin "4") (pinfunction "4_4") (pintype "passive"))
      (node (ref "CZ3") (pin "6") (pinfunction "6_6") (pintype "passive"))
      (node (ref "CZ3") (pin "8") (pinfunction "8_8") (pintype "passive"))
      (node (ref "U1") (pin "3") (pinfunction "PC0_3") (pintype "bidirectional"))
    )
    (net (code "4") (name "/COL1") (class "Default")
      (node (ref "CZ1") (pin "10") (pinfunction "10_10") (pintype "passive"))
      (node (ref "CZ1") (pin "12") (pinfunction "12_12") (pintype "passive"))
      (node (ref "CZ1") (pin "14") (pinfunction "14_14") (pintype "passive"))
      (node (ref "CZ1") (pin "16") (pinfunction "16_16") (pintype "passive"))
      (node (ref "CZ3") (pin "10") (pinfunction "10_10") (pintype "passive"))
      (node (ref "CZ3") (pin "12") (pinfunction "12_12") (pintype "passive"))
      (node (ref "CZ3") (pin "14") (pinfunction "14_14") (pintype "passive"))
      (node (ref "CZ3") (pin "16") (pinfunction "16_16") (pintype "passive"))
      (node (ref "U1") (pin "4") (pinfunction "PC3_4") (pintype "bidirectional"))
    )
    (net (code "5") (name "/COL2") (class "Default")
      (node (ref "CZ1") (pin "18") (pinfunction "18_18") (pintype "passive"))
      (node (ref "CZ1") (pin "20") (pinfunction "20_20") (pintype "passive"))
      (node (ref "CZ1") (pin "22") (pinfunction "22_22") (pintype "passive"))
      (node (ref "CZ1") (pin "24") (pinfunction "24_24") (pintype "passive"))
      (node (ref "CZ3") (pin "18") (pinfunction "18_18") (pintype "passive"))
      (node (ref "CZ3") (pin "20") (pinfunction "20_20") (pintype "passive"))
      (node (ref "CZ3") (pin "22") (pinfunction "22_22") (pintype "passive"))
      (node (ref "CZ3") (pin "24") (pinfunction "24_24") (pintype "passive"))
      (node (ref "U1") (pin "5") (pinfunction "PA0_5") (pintype "bidirectional"))
    )
    (net (code "6") (name "/COL3") (class "Default")
      (node (ref "CZ1") (pin "26") (pinfunction "26_26") (pintype "passive"))
      (node (ref "CZ1") (pin "28") (pinfunction "28_28") (pintype "passive"))
      (node (ref "CZ1") (pin "30") (pinfunction "30_30") (pintype "passive"))
      (node (ref "CZ1") (pin "32") (pinfunction "32_32") (pintype "passive"))
      (node (ref "CZ3") (pin "26") (pinfunction "26_26") (pintype "passive"))
      (node (ref "CZ3") (pin "28") (pinfunction "28_28") (pintype "passive"))
      (node (ref "CZ3") (pin "30") (pinfunction "30_30") (pintype "passive"))
      (node (ref "CZ3") (pin "32") (pinfunction "32_32") (pintype "passive"))
      (node (ref "U1") (pin "6") (pinfunction "PA1_6") (pintype "bidirectional"))
    )
    (net (code "7") (name "/COL4") (class "Default")
      (node (ref "CZ2") (pin "2") (pinfunction "2_2") (pintype "passive"))
      (node (ref "CZ2") (pin "4") (pinfunction "4_4") (pintype "passive"))
      (node (ref "CZ2") (pin "6") (pinfunction "6_6") (pintype "passive"))
      (node (ref "CZ2") (pin "8") (pinfunction "8_8") (pintype "passive"))
      (node (ref "CZ4") (pin "2") (pinfunction "2_2") (pintype "passive"))
      (node (ref "CZ4") (pin "4") (pinfunction "4_4") (pintype "passive"))
      (node (ref "CZ4") (pin "6") (pinfunction "6_6") (pintype "passive"))
      (node (ref "CZ4") (pin "8") (pinfunction "8_8") (pintype "passive"))
      (node (ref "U1") (pin "7") (pinfunction "PA2_7") (pintype "bidirectional"))
    )
    (net (code "8") (name "/COL5") (class "Default")
      (node (ref "CZ2") (pin "10") (pinfunction "10_10") (pintype "passive"))
      (node (ref "CZ2") (pin "12") (pinfunction "12_12") (pintype "passive"))
      (node (ref "CZ2") (pin "14") (pinfunction "14_14") (pintype "passive"))
      (node (ref "CZ2") (pin "16") (pinfunction "16_16") (pintype "passive"))
      (node (ref "CZ4") (pin "10") (pinfunction "10_10") (pintype "passive"))
      (node (ref "CZ4") (pin "12") (pinfunction "12_12") (pintype "passive"))
      (node (ref "CZ4") (pin "14") (pinfunction "14_14") (pintype "passive"))
      (node (ref "CZ4") (pin "16") (pinfunction "16_16") (pintype "passive"))
      (node (ref "U1") (pin "8") (pinfunction "PA3_8") (pintype "bidirectional"))
    )
    (net (code "9") (name "/COL6") (class "Default")
      (node (ref "CZ2") (pin "18") (pinfunction "18_18") (pintype "passive"))
      (node (ref "CZ2") (pin "20") (pinfunction "20_20") (pintype "passive"))
      (node (ref "CZ2") (pin "22") (pinfunction "22_22") (pintype "passive"))
      (node (ref "CZ2") (pin "24") (pinfunction "24_24") (pintype "passive"))
      (node (ref "CZ4") (pin "18") (pinfunction "18_18") (pintype "passive"))
      (node (ref "CZ4") (pin "20") (pinfunction "20_20") (pintype "passive"))
      (node (ref "CZ4") (pin "22") (pinfunction "22_22") (pintype "passive"))
      (node (ref "CZ4") (pin "24") (pinfunction "24_24") (pintype "passive"))
      (node (ref "U1") (pin "9") (pinfunction "PA4/CS_9") (pintype "bidirectional"))
    )
    (net (code "10") (name "/COL7") (class "Default")
      (node (ref "CZ2") (pin "26") (pinfunction "26_26") (pintype "passive"))
      (node (ref "CZ2") (pin "28") (pinfunction "28_28") (pintype "passive"))
      (node (ref "CZ2") (pin "30") (pinfunction "30_30") (pintype "passive"))
      (node (ref "CZ2") (pin "32") (pinfunction "32_32") (pintype "passive"))
      (node (ref "CZ4") (pin "26") (pinfunction "26_26") (pintype "passive"))
      (node (ref "CZ4") (pin "28") (pinfunction "28_28") (pintype "passive"))
      (node (ref "CZ4") (pin "30") (pinfunction "30_30") (pintype "passive"))
      (node (ref "CZ4") (pin "32") (pinfunction "32_32") (pintype "passive"))
      (node (ref "U1") (pin "10") (pinfunction "PA5/SCK_10") (pintype "bidirectional"))
    )
    (net (code "11") (name "/IO.DCK") (class "Default")
      (node (ref "P1") (pin "1") (pinfunction "1_1") (pintype "passive"))
      (node (ref "U1") (pin "24") (pinfunction "PC19/DCK_24") (pintype "bidirectional"))
    )
    (net (code "12") (name "/IO.DIO") (class "Default")
      (node (ref "P1") (pin "2") (pinfunction "2_2") (pintype "passive"))
      (node (ref "U1") (pin "25") (pinfunction "PC18/DIO_25") (pintype "bidirectional"))
    )
    (net (code "13") (name "/LED.DIN") (class "Default")
      (node (ref "D1") (pin "3") (pinfunction "Di_3") (pintype "input"))
      (node (ref "U1") (pin "12") (pinfunction "PA7/MOSI_12") (pintype "bidirectional"))
    )
    (net (code "14") (name "/LED.DOUT") (class "Default")
      (node (ref "D128") (pin "1") (pinfunction "Do_1") (pintype "output"))
    )
    (net (code "15") (name "/ROW0") (class "Default")
      (node (ref "D17") (pin "A") (pinfunction "A_A") (pintype "passive"))
      (node (ref "D18") (pin "A") (pinfunction "A_A") (pintype "passive"))
      (node (ref "D33") (pin "A") (pinfunction "A_A") (pintype "passive"))
      (node (ref "D34") (pin "A") (pinfunction "A_A") (pintype "passive"))
      (node (ref "D49") (pin "A") (pinfunction "A_A") (pintype "passive"))
      (node (ref "D50") (pin "A") (pinfunction "A_A") (pintype "passive"))
      (node (ref "D65") (pin "A") (pinfunction "A_A") (pintype "passive"))
      (node (ref "D66") (pin "A") (pinfunction "A_A") (pintype "passive"))
      (node (ref "U1") (pin "23") (pinfunction "PB12_23") (pintype "bidirectional"))
    )
    (net (code "16") (name "/ROW1") (class "Default")
      (node (ref "D13") (pin "A") (pinfunction "A_A") (pintype "passive"))
      (node (ref "D14") (pin "A") (pinfunction "A_A") (pintype "passive"))
      (node (ref "D29") (pin "A") (pinfunction "A_A") (pintype "passive"))
      (node (ref "D30") (pin "A") (pinfunction "A_A") (pintype "passive"))
      (node (ref "D45") (pin "A") (pinfunction "A_A") (pintype "passive"))
      (node (ref "D46") (pin "A") (pinfunction "A_A") (pintype "passive"))
      (node (ref "D61") (pin "A") (pinfunction "A_A") (pintype "passive"))
      (node (ref "D62") (pin "A") (pinfunction "A_A") (pintype "passive"))
      (node (ref "U1") (pin "22") (pinfunction "PB11_22") (pintype "bidirectional"))
    )
    (net (code "17") (name "/ROW2") (class "Default")
      (node (ref "D10") (pin "A") (pinfunction "A_A") (pintype "passive"))
      (node (ref "D25") (pin "A") (pinfunction "A_A") (pintype "passive"))
      (node (ref "D26") (pin "A") (pinfunction "A_A") (pintype "passive"))
      (node (ref "D41") (pin "A") (pinfunction "A_A") (pintype "passive"))
      (node (ref "D42") (pin "A") (pinfunction "A_A") (pintype "passive"))
      (node (ref "D57") (pin "A") (pinfunction "A_A") (pintype "passive"))
      (node (ref "D58") (pin "A") (pinfunction "A_A") (pintype "passive"))
      (node (ref "D9") (pin "A") (pinfunction "A_A") (pintype "passive"))
      (node (ref "U1") (pin "21") (pinfunction "PB10_21") (pintype "bidirectional"))
    )
    (net (code "18") (name "/ROW3") (class "Default")
      (node (ref "D21") (pin "A") (pinfunction "A_A") (pintype "passive"))
      (node (ref "D22") (pin "A") (pinfunction "A_A") (pintype "passive"))
      (node (ref "D37") (pin "A") (pinfunction "A_A") (pintype "passive"))
      (node (ref "D38") (pin "A") (pinfunction "A_A") (pintype "passive"))
      (node (ref "D5") (pin "A") (pinfunction "A_A") (pintype "passive"))
      (node (ref "D53") (pin "A") (pinfunction "A_A") (pintype "passive"))
      (node (ref "D54") (pin "A") (pinfunction "A_A") (pintype "passive"))
      (node (ref "D6") (pin "A") (pinfunction "A_A") (pintype "passive"))
      (node (ref "U1") (pin "20") (pinfunction "PB9_20") (pintype "bidirectional"))
    )
    (net (code "19") (name "/ROW4") (class "Default")
      (node (ref "D19") (pin "A") (pinfunction "A_A") (pintype "passive"))
      (node (ref "D20") (pin "A") (pinfunction "A_A") (pintype "passive"))
      (node (ref "D35") (pin "A") (pinfunction "A_A") (pintype "passive"))
      (node (ref "D36") (pin "A") (pinfunction "A_A") (pintype "passive"))
      (node (ref "D51") (pin "A") (pinfunction "A_A") (pintype "passive"))
      (node (ref "D52") (pin "A") (pinfunction "A_A") (pintype "passive"))
      (node (ref "D67") (pin "A") (pinfunction "A_A") (pintype "passive"))
      (node (ref "D68") (pin "A") (pinfunction "A_A") (pintype "passive"))
      (node (ref "U1") (pin "19") (pinfunction "PB8_19") (pintype "bidirectional"))
    )
    (net (code "20") (name "/ROW5") (class "Default")
      (node (ref "D15") (pin "A") (pinfunction "A_A") (pintype "passive"))
      (node (ref "D16") (pin "A") (pinfunction "A_A") (pintype "passive"))
      (node (ref "D31") (pin "A") (pinfunction "A_A") (pintype "passive"))
      (node (ref "D32") (pin "A") (pinfunction "A_A") (pintype "passive"))
      (node (ref "D47") (pin "A") (pinfunction "A_A") (pintype "passive"))
      (node (ref "D48") (pin "A") (pinfunction "A_A") (pintype "passive"))
      (node (ref "D63") (pin "A") (pinfunction "A_A") (pintype "passive"))
      (node (ref "D64") (pin "A") (pinfunction "A_A") (pintype "passive"))
      (node (ref "U1") (pin "18") (pinfunction "PB7_18") (pintype "bidirectional"))
    )
    (net (code "21") (name "/ROW6") (class "Default")
      (node (ref "D11") (pin "A") (pinfunction "A_A") (pintype "passive"))
      (node (ref "D12") (pin "A") (pinfunction "A_A") (pintype "passive"))
      (node (ref "D27") (pin "A") (pinfunction "A_A") (pintype "passive"))
      (node (ref "D28") (pin "A") (pinfunction "A_A") (pintype "passive"))
      (node (ref "D43") (pin "A") (pinfunction "A_A") (pintype "passive"))
      (node (ref "D44") (pin "A") (pinfunction "A_A") (pintype "passive"))
      (node (ref "D59") (pin "A") (pinfunction "A_A") (pintype "passive"))
      (node (ref "D60") (pin "A") (pinfunction "A_A") (pintype "passive"))
      (node (ref "U1") (pin "17") (pinfunction "PB6_17") (pintype "bidirectional"))
    )
    (net (code "22") (name "/ROW7") (class "Default")
      (node (ref "D23") (pin "A") (pinfunction "A_A") (pintype "passive"))
      (node (ref "D24") (pin "A") (pinfunction "A_A") (pintype "passive"))
      (node (ref "D39") (pin "A") (pinfunction "A_A") (pintype "passive"))
      (node (ref "D40") (pin "A") (pinfunction "A_A") (pintype "passive"))
      (node (ref "D55") (pin "A") (pinfunction "A_A") (pintype "passive"))
      (node (ref "D56") (pin "A") (pinfunction "A_A") (pintype "passive"))
      (node (ref "D7") (pin "A") (pinfunction "A_A") (pintype "passive"))
      (node (ref "D8") (pin "A") (pinfunction "A_A") (pintype "passive"))
      (node (ref "U1") (pin "16") (pinfunction "PB1_16") (pintype "bidirectional"))
    )
    (net (code "23") (name "/USB.D_n") (class "Default")
      (node (ref "J1") (pin "A7") (pinfunction "Dn1_A7") (pintype "passive"))
      (node (ref "J1") (pin "B7") (pinfunction "Dn2_B7") (pintype "passive"))
      (node (ref "U1") (pin "26") (pinfunction "PC16/UD-_26") (pintype "bidirectional"))
    )
    (net (code "24") (name "/USB.D_p") (class "Default")
      (node (ref "J1") (pin "A6") (pinfunction "Dp1_A6") (pintype "passive"))
      (node (ref "J1") (pin "B6") (pinfunction "Dp2_B6") (pintype "passive"))
      (node (ref "SW1") (pin "2") (pinfunction "2_2") (pintype "passive"))
      (node (ref "U1") (pin "27") (pinfunction "PC17/UD+_27") (pintype "bidirectional"))
    )
    (net (code "25") (name "GND") (class "Default")
      (node (ref "C1") (pin "2") (pinfunction "2_2") (pintype "passive"))
      (node (ref "C10") (pin "2") (pinfunction "2_2") (pintype "passive"))
      (node (ref "C11") (pin "2") (pinfunction "2_2") (pintype "passive"))
      (node (ref "C12") (pin "2") (pinfunction "2_2") (pintype "passive"))
      (node (ref "C13") (pin "2") (pinfunction "2_2") (pintype "passive"))
      (node (ref "C14") (pin "2") (pinfunction "2_2") (pintype "passive"))
      (node (ref "C15") (pin "2") (pinfunction "2_2") (pintype "passive"))
      (node (ref "C16") (pin "2") (pinfunction "2_2") (pintype "passive"))
      (node (ref "C17") (pin "2") (pinfunction "2_2") (pintype "passive"))
      (node (ref "C18") (pin "2") (pinfunction "2_2") (pintype "passive"))
      (node (ref "C19") (pin "2") (pinfunction "2_2") (pintype "passive"))
      (node (ref "C2") (pin "2") (pinfunction "2_2") (pintype "passive"))
      (node (ref "C20") (pin "2") (pinfunction "2_2") (pintype "passive"))
      (node (ref "C21") (pin "2") (pinfunction "2_2") (pintype "passive"))
      (node (ref "C22") (pin "2") (pinfunction "2_2") (pintype "passive"))
      (node (ref "C23") (pin "2") (pinfunction "2_2") (pintype "passive"))
      (node (ref "C24") (pin "2") (pinfunction "2_2") (pintype "passive"))
      (node (ref "C25") (pin "2") (pinfunction "2_2") (pintype "passive"))
      (node (ref "C26") (pin "2") (pinfunction "2_2") (pintype "passive"))
      (node (ref "C27") (pin "2") (pinfunction "2_2") (pintype "passive"))
      (node (ref "C28") (pin "2") (pinfunction "2_2") (pintype "passive"))
      (node (ref "C29") (pin "2") (pinfunction "2_2") (pintype "passive"))
      (node (ref "C3") (pin "2") (pinfunction "2_2") (pintype "passive"))
      (node (ref "C30") (pin "2") (pinfunction "2_2") (pintype "passive"))
      (node (ref "C31") (pin "2") (pinfunction "2_2") (pintype "passive"))
      (node (ref "C32") (pin "2") (pinfunction "2_2") (pintype "passive"))
      (node (ref "C33") (pin "2") (pinfunction "2_2") (pintype "passive"))
      (node (ref "C34") (pin "2") (pinfunction "2_2") (pintype "passive"))
      (node (ref "C35") (pin "2") (pinfunction "2_2") (pintype "passive"))
      (node (ref "C36") (pin "2") (pinfunction "2_2") (pintype "passive"))
      (node (ref "C37") (pin "2") (pinfunction "2_2") (pintype "passive"))
      (node (ref "C38") (pin "2") (pinfunction "2_2") (pintype "passive"))
      (node (ref "C39") (pin "2") (pinfunction "2_2") (pintype "passive"))
      (node (ref "C4") (pin "2") (pinfunction "2_2") (pintype "passive"))
      (node (ref "C40") (pin "2") (pinfunction "2_2") (pintype "passive"))
      (node (ref "C41") (pin "2") (pinfunction "2_2") (pintype "passive"))
      (node (ref "C42") (pin "2") (pinfunction "2_2") (pintype "passive"))
      (node (ref "C43") (pin "2") (pinfunction "2_2") (pintype "passive"))
      (node (ref "C44") (pin "2") (pinfunction "2_2") (pintype "passive"))
      (node (ref "C45") (pin "2") (pinfunction "2_2") (pintype "passive"))
      (node (ref "C46") (pin "2") (pinfunction "2_2") (pintype "passive"))
      (node (ref "C47") (pin "2") (pinfunction "2_2") (pintype "passive"))
      (node (ref "C48") (pin "2") (pinfunction "2_2") (pintype "passive"))
      (node (ref "C49") (pin "2") (pinfunction "2_2") (pintype "passive"))
      (node (ref "C5") (pin "2") (pinfunction "2_2") (pintype "passive"))
      (node (ref "C50") (pin "2") (pinfunction "2_2") (pintype "passive"))
      (node (ref "C51") (pin "2") (pinfunction "2_2") (pintype "passive"))
      (node (ref "C52") (pin "2") (pinfunction "2_2") (pintype "passive"))
      (node (ref "C53") (pin "2") (pinfunction "2_2") (pintype "passive"))
      (node (ref "C54") (pin "2") (pinfunction "2_2") (pintype "passive"))
      (node (ref "C55") (pin "2") (pinfunction "2_2") (pintype "passive"))
      (node (ref "C56") (pin "2") (pinfunction "2_2") (pintype "passive"))
      (node (ref "C57") (pin "2") (pinfunction "2_2") (pintype "passive"))
      (node (ref "C58") (pin "2") (pinfunction "2_2") (pintype "passive"))
      (node (ref "C59") (pin "2") (pinfunction "2_2") (pintype "passive"))
      (node (ref "C6") (pin "2") (pinfunction "2_2") (pintype "passive"))
      (node (ref "C60") (pin "2") (pinfunction "2_2") (pintype "passive"))
      (node (ref "C61") (pin "2") (pinfunction "2_2") (pintype "passive"))
      (node (ref "C62") (pin "2") (pinfunction "2_2") (pintype "passive"))
      (node (ref "C63") (pin "2") (pinfunction "2_2") (pintype "passive"))
      (node (ref "C64") (pin "2") (pinfunction "2_2") (pintype "passive"))
      (node (ref "C65") (pin "2") (pinfunction "2_2") (pintype "passive"))
      (node (ref "C66") (pin "2") (pinfunction "2_2") (pintype "passive"))
      (node (ref "C7") (pin "2") (pinfunction "2_2") (pintype "passive"))
      (node (ref "C8") (pin "2") (pinfunction "2_2") (pintype "passive"))
      (node (ref "C9") (pin "2") (pinfunction "2_2") (pintype "passive"))
      (node (ref "D1") (pin "2") (pinfunction "G_2") (pintype "power_in"))
      (node (ref "D100") (pin "2") (pinfunction "G_2") (pintype "power_in"))
      (node (ref "D101") (pin "2") (pinfunction "G_2") (pintype "power_in"))
      (node (ref "D102") (pin "2") (pinfunction "G_2") (pintype "power_in"))
      (node (ref "D103") (pin "2") (pinfunction "G_2") (pintype "power_in"))
      (node (ref "D104") (pin "2") (pinfunction "G_2") (pintype "power_in"))
      (node (ref "D105") (pin "2") (pinfunction "G_2") (pintype "power_in"))
      (node (ref "D106") (pin "2") (pinfunction "G_2") (pintype "power_in"))
      (node (ref "D107") (pin "2") (pinfunction "G_2") (pintype "power_in"))
      (node (ref "D108") (pin "2") (pinfunction "G_2") (pintype "power_in"))
      (node (ref "D109") (pin "2") (pinfunction "G_2") (pintype "power_in"))
      (node (ref "D110") (pin "2") (pinfunction "G_2") (pintype "power_in"))
      (node (ref "D111") (pin "2") (pinfunction "G_2") (pintype "power_in"))
      (node (ref "D112") (pin "2") (pinfunction "G_2") (pintype "power_in"))
      (node (ref "D113") (pin "2") (pinfunction "G_2") (pintype "power_in"))
      (node (ref "D114") (pin "2") (pinfunction "G_2") (pintype "power_in"))
      (node (ref "D115") (pin "2") (pinfunction "G_2") (pintype "power_in"))
      (node (ref "D116") (pin "2") (pinfunction "G_2") (pintype "power_in"))
      (node (ref "D117") (pin "2") (pinfunction "G_2") (pintype "power_in"))
      (node (ref "D118") (pin "2") (pinfunction "G_2") (pintype "power_in"))
      (node (ref "D119") (pin "2") (pinfunction "G_2") (pintype "power_in"))
      (node (ref "D120") (pin "2") (pinfunction "G_2") (pintype "power_in"))
      (node (ref "D121") (pin "2") (pinfunction "G_2") (pintype "power_in"))
      (node (ref "D122") (pin "2") (pinfunction "G_2") (pintype "power_in"))
      (node (ref "D123") (pin "2") (pinfunction "G_2") (pintype "power_in"))
      (node (ref "D124") (pin "2") (pinfunction "G_2") (pintype "power_in"))
      (node (ref "D125") (pin "2") (pinfunction "G_2") (pintype "power_in"))
      (node (ref "D126") (pin "2") (pinfunction "G_2") (pintype "power_in"))
      (node (ref "D127") (pin "2") (pinfunction "G_2") (pintype "power_in"))
      (node (ref "D128") (pin "2") (pinfunction "G_2") (pintype "power_in"))
      (node (ref "D2") (pin "2") (pinfunction "G_2") (pintype "power_in"))
      (node (ref "D3") (pin "2") (pinfunction "G_2") (pintype "power_in"))
      (node (ref "D4") (pin "2") (pinfunction "G_2") (pintype "power_in"))
      (node (ref "D69") (pin "2") (pinfunction "G_2") (pintype "power_in"))
      (node (ref "D70") (pin "2") (pinfunction "G_2") (pintype "power_in"))
      (node (ref "D71") (pin "2") (pinfunction "G_2") (pintype "power_in"))
      (node (ref "D72") (pin "2") (pinfunction "G_2") (pintype "power_in"))
      (node (ref "D73") (pin "2") (pinfunction "G_2") (pintype "power_in"))
      (node (ref "D74") (pin "2") (pinfunction "G_2") (pintype "power_in"))
      (node (ref "D75") (pin "2") (pinfunction "G_2") (pintype "power_in"))
      (node (ref "D76") (pin "2") (pinfunction "G_2") (pintype "power_in"))
      (node (ref "D77") (pin "2") (pinfunction "G_2") (pintype "power_in"))
      (node (ref "D78") (pin "2") (pinfunction "G_2") (pintype "power_in"))
      (node (ref "D79") (pin "2") (pinfunction "G_2") (pintype "power_in"))
      (node (ref "D80") (pin "2") (pinfunction "G_2") (pintype "power_in"))
      (node (ref "D81") (pin "2") (pinfunction "G_2") (pintype "power_in"))
      (node (ref "D82") (pin "2") (pinfunction "G_2") (pintype "power_in"))
      (node (ref "D83") (pin "2") (pinfunction "G_2") (pintype "power_in"))
      (node (ref "D84") (pin "2") (pinfunction "G_2") (pintype "power_in"))
      (node (ref "D85") (pin "2") (pinfunction "G_2") (pintype "power_in"))
      (node (ref "D86") (pin "2") (pinfunction "G_2") (pintype "power_in"))
      (node (ref "D87") (pin "2") (pinfunction "G_2") (pintype "power_in"))
      (node (ref "D88") (pin "2") (pinfunction "G_2") (pintype "power_in"))
      (node (ref "D89") (pin "2") (pinfunction "G_2") (pintype "power_in"))
      (node (ref "D90") (pin "2") (pinfunction "G_2") (pintype "power_in"))
      (node (ref "D91") (pin "2") (pinfunction "G_2") (pintype "power_in"))
      (node (ref "D92") (pin "2") (pinfunction "G_2") (pintype "power_in"))
      (node (ref "D93") (pin "2") (pinfunction "G_2") (pintype "power_in"))
      (node (ref "D94") (pin "2") (pinfunction "G_2") (pintype "power_in"))
      (node (ref "D95") (pin "2") (pinfunction "G_2") (pintype "power_in"))
      (node (ref "D96") (pin "2") (pinfunction "G_2") (pintype "power_in"))
      (node (ref "D97") (pin "2") (pinfunction "G_2") (pintype "power_in"))
      (node (ref "D98") (pin "2") (pinfunction "G_2") (pintype "power_in"))
      (node (ref "D99") (pin "2") (pinfunction "G_2") (pintype "power_in"))
      (node (ref "J1") (pin "A1") (pinfunction "GND_A1") (pintype "passive"))
      (node (ref "J1") (pin "A12") (pinfunction "GND_A12") (pintype "passive"))
      (node (ref "J1") (pin "B1") (pinfunction "GND_B1") (pintype "passive"))
      (node (ref "J1") (pin "B12") (pinfunction "GND_B12") (pintype "passive"))
      (node (ref "J1") (pin "MH1") (pinfunction "Tab_MH1") (pintype "passive"))
      (node (ref "J1") (pin "MH2") (pinfunction "Tab_MH2") (pintype "passive"))
      (node (ref "J1") (pin "MH3") (pinfunction "Tab_MH3") (pintype "passive"))
      (node (ref "J1") (pin "MH4") (pinfunction "Tab_MH4") (pintype "passive"))
      (node (ref "P2") (pin "1") (pinfunction "1_1") (pintype "passive"))
      (node (ref "R2") (pin "2") (pinfunction "2_2") (pintype "passive"))
      (node (ref "R3") (pin "2") (pinfunction "2_2") (pintype "passive"))
      (node (ref "U1") (pin "29") (pinfunction "GND_29") (pintype "power_in"))
    )
    (net (code "26") (name "Net-(CZ1-Pad1)") (class "Default")
      (node (ref "CZ1") (pin "1") (pinfunction "1_1") (pintype "passive"))
      (node (ref "D17") (pin "C") (pinfunction "C_C") (pintype "passive"))
    )
    (net (code "27") (name "Net-(CZ1-Pad3)") (class "Default")
      (node (ref "CZ1") (pin "3") (pinfunction "3_3") (pintype "passive"))
      (node (ref "D13") (pin "C") (pinfunction "C_C") (pintype "passive"))
    )
    (net (code "28") (name "Net-(CZ1-Pad5)") (class "Default")
      (node (ref "CZ1") (pin "5") (pinfunction "5_5") (pintype "passive"))
      (node (ref "D9") (pin "C") (pinfunction "C_C") (pintype "passive"))
    )
    (net (code "29") (name "Net-(CZ1-Pad7)") (class "Default")
      (node (ref "CZ1") (pin "7") (pinfunction "7_7") (pintype "passive"))
      (node (ref "D5") (pin "C") (pinfunction "C_C") (pintype "passive"))
    )
    (net (code "30") (name "Net-(CZ1-Pad9)") (class "Default")
      (node (ref "CZ1") (pin "9") (pinfunction "9_9") (pintype "passive"))
      (node (ref "D33") (pin "C") (pinfunction "C_C") (pintype "passive"))
    )
    (net (code "31") (name "Net-(CZ1-Pad11)") (class "Default")
      (node (ref "CZ1") (pin "11") (pinfunction "11_11") (pintype "passive"))
      (node (ref "D29") (pin "C") (pinfunction "C_C") (pintype "passive"))
    )
    (net (code "32") (name "Net-(CZ1-Pad13)") (class "Default")
      (node (ref "CZ1") (pin "13") (pinfunction "13_13") (pintype "passive"))
      (node (ref "D25") (pin "C") (pinfunction "C_C") (pintype "passive"))
    )
    (net (code "33") (name "Net-(CZ1-Pad15)") (class "Default")
      (node (ref "CZ1") (pin "15") (pinfunction "15_15") (pintype "passive"))
      (node (ref "D21") (pin "C") (pinfunction "C_C") (pintype "passive"))
    )
    (net (code "34") (name "Net-(CZ1-Pad17)") (class "Default")
      (node (ref "CZ1") (pin "17") (pinfunction "17_17") (pintype "passive"))
      (node (ref "D49") (pin "C") (pinfunction "C_C") (pintype "passive"))
    )
    (net (code "35") (name "Net-(CZ1-Pad19)") (class "Default")
      (node (ref "CZ1") (pin "19") (pinfunction "19_19") (pintype "passive"))
      (node (ref "D45") (pin "C") (pinfunction "C_C") (pintype "passive"))
    )
    (net (code "36") (name "Net-(CZ1-Pad21)") (class "Default")
      (node (ref "CZ1") (pin "21") (pinfunction "21_21") (pintype "passive"))
      (node (ref "D41") (pin "C") (pinfunction "C_C") (pintype "passive"))
    )
    (net (code "37") (name "Net-(CZ1-Pad23)") (class "Default")
      (node (ref "CZ1") (pin "23") (pinfunction "23_23") (pintype "passive"))
      (node (ref "D37") (pin "C") (pinfunction "C_C") (pintype "passive"))
    )
    (net (code "38") (name "Net-(CZ1-Pad25)") (class "Default")
      (node (ref "CZ1") (pin "25") (pinfunction "25_25") (pintype "passive"))
      (node (ref "D65") (pin "C") (pinfunction "C_C") (pintype "passive"))
    )
    (net (code "39") (name "Net-(CZ1-Pad27)") (class "Default")
      (node (ref "CZ1") (pin "27") (pinfunction "27_27") (pintype "passive"))
      (node (ref "D61") (pin "C") (pinfunction "C_C") (pintype "passive"))
    )
    (net (code "40") (name "Net-(CZ1-Pad29)") (class "Default")
      (node (ref "CZ1") (pin "29") (pinfunction "29_29") (pintype "passive"))
      (node (ref "D57") (pin "C") (pinfunction "C_C") (pintype "passive"))
    )
    (net (code "41") (name "Net-(CZ1-Pad31)") (class "Default")
      (node (ref "CZ1") (pin "31") (pinfunction "31_31") (pintype "passive"))
      (node (ref "D53") (pin "C") (pinfunction "C_C") (pintype "passive"))
    )
    (net (code "42") (name "Net-(CZ2-Pad1)") (class "Default")
      (node (ref "CZ2") (pin "1") (pinfunction "1_1") (pintype "passive"))
      (node (ref "D18") (pin "C") (pinfunction "C_C") (pintype "passive"))
    )
    (net (code "43") (name "Net-(CZ2-Pad3)") (class "Default")
      (node (ref "CZ2") (pin "3") (pinfunction "3_3") (pintype "passive"))
      (node (ref "D14") (pin "C") (pinfunction "C_C") (pintype "passive"))
    )
    (net (code "44") (name "Net-(CZ2-Pad5)") (class "Default")
      (node (ref "CZ2") (pin "5") (pinfunction "5_5") (pintype "passive"))
      (node (ref "D10") (pin "C") (pinfunction "C_C") (pintype "passive"))
    )
    (net (code "45") (name "Net-(CZ2-Pad7)") (class "Default")
      (node (ref "CZ2") (pin "7") (pinfunction "7_7") (pintype "passive"))
      (node (ref "D6") (pin "C") (pinfunction "C_C") (pintype "passive"))
    )
    (net (code "46") (name "Net-(CZ2-Pad9)") (class "Default")
      (node (ref "CZ2") (pin "9") (pinfunction "9_9") (pintype "passive"))
      (node (ref "D34") (pin "C") (pinfunction "C_C") (pintype "passive"))
    )
    (net (code "47") (name "Net-(CZ2-Pad11)") (class "Default")
      (node (ref "CZ2") (pin "11") (pinfunction "11_11") (pintype "passive"))
      (node (ref "D30") (pin "C") (pinfunction "C_C") (pintype "passive"))
    )
    (net (code "48") (name "Net-(CZ2-Pad13)") (class "Default")
      (node (ref "CZ2") (pin "13") (pinfunction "13_13") (pintype "passive"))
      (node (ref "D26") (pin "C") (pinfunction "C_C") (pintype "passive"))
    )
    (net (code "49") (name "Net-(CZ2-Pad15)") (class "Default")
      (node (ref "CZ2") (pin "15") (pinfunction "15_15") (pintype "passive"))
      (node (ref "D22") (pin "C") (pinfunction "C_C") (pintype "passive"))
    )
    (net (code "50") (name "Net-(CZ2-Pad17)") (class "Default")
      (node (ref "CZ2") (pin "17") (pinfunction "17_17") (pintype "passive"))
      (node (ref "D50") (pin "C") (pinfunction "C_C") (pintype "passive"))
    )
    (net (code "51") (name "Net-(CZ2-Pad19)") (class "Default")
      (node (ref "CZ2") (pin "19") (pinfunction "19_19") (pintype "passive"))
      (node (ref "D46") (pin "C") (pinfunction "C_C") (pintype "passive"))
    )
    (net (code "52") (name "Net-(CZ2-Pad21)") (class "Default")
      (node (ref "CZ2") (pin "21") (pinfunction "21_21") (pintype "passive"))
      (node (ref "D42") (pin "C") (pinfunction "C_C") (pintype "passive"))
    )
    (net (code "53") (name "Net-(CZ2-Pad23)") (class "Default")
      (node (ref "CZ2") (pin "23") (pinfunction "23_23") (pintype "passive"))
      (node (ref "D38") (pin "C") (pinfunction "C_C") (pintype "passive"))
    )
    (net (code "54") (name "Net-(CZ2-Pad25)") (class "Default")
      (node (ref "CZ2") (pin "25") (pinfunction "25_25") (pintype "passive"))
      (node (ref "D66") (pin "C") (pinfunction "C_C") (pintype "passive"))
    )
    (net (code "55") (name "Net-(CZ2-Pad27)") (class "Default")
      (node (ref "CZ2") (pin "27") (pinfunction "27_27") (pintype "passive"))
      (node (ref "D62") (pin "C") (pinfunction "C_C") (pintype "passive"))
    )
    (net (code "56") (name "Net-(CZ2-Pad29)") (class "Default")
      (node (ref "CZ2") (pin "29") (pinfunction "29_29") (pintype "passive"))
      (node (ref "D58") (pin "C") (pinfunction "C_C") (pintype "passive"))
    )
    (net (code "57") (name "Net-(CZ2-Pad31)") (class "Default")
      (node (ref "CZ2") (pin "31") (pinfunction "31_31") (pintype "passive"))
      (node (ref "D54") (pin "C") (pinfunction "C_C") (pintype "passive"))
    )
    (net (code "58") (name "Net-(CZ3-Pad1)") (class "Default")
      (node (ref "CZ3") (pin "1") (pinfunction "1_1") (pintype "passive"))
      (node (ref "D19") (pin "C") (pinfunction "C_C") (pintype "passive"))
    )
    (net (code "59") (name "Net-(CZ3-Pad3)") (class "Default")
      (node (ref "CZ3") (pin "3") (pinfunction "3_3") (pintype "passive"))
      (node (ref "D15") (pin "C") (pinfunction "C_C") (pintype "passive"))
    )
    (net (code "60") (name "Net-(CZ3-Pad5)") (class "Default")
      (node (ref "CZ3") (pin "5") (pinfunction "5_5") (pintype "passive"))
      (node (ref "D11") (pin "C") (pinfunction "C_C") (pintype "passive"))
    )
    (net (code "61") (name "Net-(CZ3-Pad7)") (class "Default")
      (node (ref "CZ3") (pin "7") (pinfunction "7_7") (pintype "passive"))
      (node (ref "D7") (pin "C") (pinfunction "C_C") (pintype "passive"))
    )
    (net (code "62") (name "Net-(CZ3-Pad9)") (class "Default")
      (node (ref "CZ3") (pin "9") (pinfunction "9_9") (pintype "passive"))
      (node (ref "D35") (pin "C") (pinfunction "C_C") (pintype "passive"))
    )
    (net (code "63") (name "Net-(CZ3-Pad11)") (class "Default")
      (node (ref "CZ3") (pin "11") (pinfunction "11_11") (pintype "passive"))
      (node (ref "D31") (pin "C") (pinfunction "C_C") (pintype "passive"))
    )
    (net (code "64") (name "Net-(CZ3-Pad13)") (class "Default")
      (node (ref "CZ3") (pin "13") (pinfunction "13_13") (pintype "passive"))
      (node (ref "D27") (pin "C") (pinfunction "C_C") (pintype "passive"))
    )
    (net (code "65") (name "Net-(CZ3-Pad15)") (class "Default")
      (node (ref "CZ3") (pin "15") (pinfunction "15_15") (pintype "passive"))
      (node (ref "D23") (pin "C") (pinfunction "C_C") (pintype "passive"))
    )
    (net (code "66") (name "Net-(CZ3-Pad17)") (class "Default")
      (node (ref "CZ3") (pin "17") (pinfunction "17_17") (pintype "passive"))
      (node (ref "D51") (pin "C") (pinfunction "C_C") (pintype "passive"))
    )
    (net (code "67") (name "Net-(CZ3-Pad19)") (class "Default")
      (node (ref "CZ3") (pin "19") (pinfunction "19_19") (pintype "passive"))
      (node (ref "D47") (pin "C") (pinfunction "C_C") (pintype "passive"))
    )
    (net (code "68") (name "Net-(CZ3-Pad21)") (class "Default")
      (node (ref "CZ3") (pin "21") (pinfunction "21_21") (pintype "passive"))
      (node (ref "D43") (pin "C") (pinfunction "C_C") (pintype "passive"))
    )
    (net (code "69") (name "Net-(CZ3-Pad23)") (class "Default")
      (node (ref "CZ3") (pin "23") (pinfunction "23_23") (pintype "passive"))
      (node (ref "D39") (pin "C") (pinfunction "C_C") (pintype "passive"))
    )
    (net (code "70") (name "Net-(CZ3-Pad25)") (class "Default")
      (node (ref "CZ3") (pin "25") (pinfunction "25_25") (pintype "passive"))
      (node (ref "D67") (pin "C") (pinfunction "C_C") (pintype "passive"))
    )
    (net (code "71") (name "Net-(CZ3-Pad27)") (class "Default")
      (node (ref "CZ3") (pin "27") (pinfunction "27_27") (pintype "passive"))
      (node (ref "D63") (pin "C") (pinfunction "C_C") (pintype "passive"))
    )
    (net (code "72") (name "Net-(CZ3-Pad29)") (class "Default")
      (node (ref "CZ3") (pin "29") (pinfunction "29_29") (pintype "passive"))
      (node (ref "D59") (pin "C") (pinfunction "C_C") (pintype "passive"))
    )
    (net (code "73") (name "Net-(CZ3-Pad31)") (class "Default")
      (node (ref "CZ3") (pin "31") (pinfunction "31_31") (pintype "passive"))
      (node (ref "D55") (pin "C") (pinfunction "C_C") (pintype "passive"))
    )
    (net (code "74") (name "Net-(CZ4-Pad1)") (class "Default")
      (node (ref "CZ4") (pin "1") (pinfunction "1_1") (pintype "passive"))
      (node (ref "D20") (pin "C") (pinfunction "C_C") (pintype "passive"))
    )
    (net (code "75") (name "Net-(CZ4-Pad3)") (class "Default")
      (node (ref "CZ4") (pin "3") (pinfunction "3_3") (pintype "passive"))
      (node (ref "D16") (pin "C") (pinfunction "C_C") (pintype "passive"))
    )
    (net (code "76") (name "Net-(CZ4-Pad5)") (class "Default")
      (node (ref "CZ4") (pin "5") (pinfunction "5_5") (pintype "passive"))
      (node (ref "D12") (pin "C") (pinfunction "C_C") (pintype "passive"))
    )
    (net (code "77") (name "Net-(CZ4-Pad7)") (class "Default")
      (node (ref "CZ4") (pin "7") (pinfunction "7_7") (pintype "passive"))
      (node (ref "D8") (pin "C") (pinfunction "C_C") (pintype "passive"))
    )
    (net (code "78") (name "Net-(CZ4-Pad9)") (class "Default")
      (node (ref "CZ4") (pin "9") (pinfunction "9_9") (pintype "passive"))
      (node (ref "D36") (pin "C") (pinfunction "C_C") (pintype "passive"))
    )
    (net (code "79") (name "Net-(CZ4-Pad11)") (class "Default")
      (node (ref "CZ4") (pin "11") (pinfunction "11_11") (pintype "passive"))
      (node (ref "D32") (pin "C") (pinfunction "C_C") (pintype "passive"))
    )
    (net (code "80") (name "Net-(CZ4-Pad13)") (class "Default")
      (node (ref "CZ4") (pin "13") (pinfunction "13_13") (pintype "passive"))
      (node (ref "D28") (pin "C") (pinfunction "C_C") (pintype "passive"))
    )
    (net (code "81") (name "Net-(CZ4-Pad15)") (class "Default")
      (node (ref "CZ4") (pin "15") (pinfunction "15_15") (pintype "passive"))
      (node (ref "D24") (pin "C") (pinfunction "C_C") (pintype "passive"))
    )
    (net (code "82") (name "Net-(CZ4-Pad17)") (class "Default")
      (node (ref "CZ4") (pin "17") (pinfunction "17_17") (pintype "passive"))
      (node (ref "D52") (pin "C") (pinfunction "C_C") (pintype "passive"))
    )
    (net (code "83") (name "Net-(CZ4-Pad19)") (class "Default")
      (node (ref "CZ4") (pin "19") (pinfunction "19_19") (pintype "passive"))
      (node (ref "D48") (pin "C") (pinfunction "C_C") (pintype "passive"))
    )
    (net (code "84") (name "Net-(CZ4-Pad21)") (class "Default")
      (node (ref "CZ4") (pin "21") (pinfunction "21_21") (pintype "passive"))
      (node (ref "D44") (pin "C") (pinfunction "C_C") (pintype "passive"))
    )
    (net (code "85") (name "Net-(CZ4-Pad23)") (class "Default")
      (node (ref "CZ4") (pin "23") (pinfunction "23_23") (pintype "passive"))
      (node (ref "D40") (pin "C") (pinfunction "C_C") (pintype "passive"))
    )
    (net (code "86") (name "Net-(CZ4-Pad25)") (class "Default")
      (node (ref "CZ4") (pin "25") (pinfunction "25_25") (pintype "passive"))
      (node (ref "D68") (pin "C") (pinfunction "C_C") (pintype "passive"))
    )
    (net (code "87") (name "Net-(CZ4-Pad27)") (class "Default")
      (node (ref "CZ4") (pin "27") (pinfunction "27_27") (pintype "passive"))
      (node (ref "D64") (pin "C") (pinfunction "C_C") (pintype "passive"))
    )
    (net (code "88") (name "Net-(CZ4-Pad29)") (class "Default")
      (node (ref "CZ4") (pin "29") (pinfunction "29_29") (pintype "passive"))
      (node (ref "D60") (pin "C") (pinfunction "C_C") (pintype "passive"))
    )
    (net (code "89") (name "Net-(CZ4-Pad31)") (class "Default")
      (node (ref "CZ4") (pin "31") (pinfunction "31_31") (pintype "passive"))
      (node (ref "D56") (pin "C") (pinfunction "C_C") (pintype "passive"))
    )
    (net (code "90") (name "Net-(D1-Do)") (class "Default")
      (node (ref "D1") (pin "1") (pinfunction "Do_1") (pintype "output"))
      (node (ref "D2") (pin "3") (pinfunction "Di_3") (pintype "input"))
    )
    (net (code "91") (name "Net-(D2-Do)") (class "Default")
      (node (ref "D2") (pin "1") (pinfunction "Do_1") (pintype "output"))
      (node (ref "D3") (pin "3") (pinfunction "Di_3") (pintype "input"))
    )
    (net (code "92") (name "Net-(D3-Do)") (class "Default")
      (node (ref "D3") (pin "1") (pinfunction "Do_1") (pintype "output"))
      (node (ref "D4") (pin "3") (pinfunction "Di_3") (pintype "input"))
    )
    (net (code "93") (name "Net-(D4-Do)") (class "Default")
      (node (ref "D4") (pin "1") (pinfunction "Do_1") (pintype "output"))
      (node (ref "D69") (pin "3") (pinfunction "Di_3") (pintype "input"))
    )
    (net (code "94") (name "Net-(D69-Do)") (class "Default")
      (node (ref "D69") (pin "1") (pinfunction "Do_1") (pintype "output"))
      (node (ref "D70") (pin "3") (pinfunction "Di_3") (pintype "input"))
    )
    (net (code "95") (name "Net-(D70-Do)") (class "Default")
      (node (ref "D70") (pin "1") (pinfunction "Do_1") (pintype "output"))
      (node (ref "D71") (pin "3") (pinfunction "Di_3") (pintype "input"))
    )
    (net (code "96") (name "Net-(D71-Do)") (class "Default")
      (node (ref "D71") (pin "1") (pinfunction "Do_1") (pintype "output"))
      (node (ref "D72") (pin "3") (pinfunction "Di_3") (pintype "input"))
    )
    (net (code "97") (name "Net-(D72-Do)") (class "Default")
      (node (ref "D72") (pin "1") (pinfunction "Do_1") (pintype "output"))
      (node (ref "D73") (pin "3") (pinfunction "Di_3") (pintype "input"))
    )
    (net (code "98") (name "Net-(D73-Do)") (class "Default")
      (node (ref "D73") (pin "1") (pinfunction "Do_1") (pintype "output"))
      (node (ref "D74") (pin "3") (pinfunction "Di_3") (pintype "input"))
    )
    (net (code "99") (name "Net-(D74-Do)") (class "Default")
      (node (ref "D74") (pin "1") (pinfunction "Do_1") (pintype "output"))
      (node (ref "D75") (pin "3") (pinfunction "Di_3") (pintype "input"))
    )
    (net (code "100") (name "Net-(D75-Do)") (class "Default")
      (node (ref "D75") (pin "1") (pinfunction "Do_1") (pintype "output"))
      (node (ref "D76") (pin "3") (pinfunction "Di_3") (pintype "input"))
    )
    (net (code "101") (name "Net-(D76-Do)") (class "Default")
      (node (ref "D76") (pin "1") (pinfunction "Do_1") (pintype "output"))
      (node (ref "D77") (pin "3") (pinfunction "Di_3") (pintype "input"))
    )
    (net (code "102") (name "Net-(D77-Do)") (class "Default")
      (node (ref "D77") (pin "1") (pinfunction "Do_1") (pintype "output"))
      (node (ref "D78") (pin "3") (pinfunction "Di_3") (pintype "input"))
    )
    (net (code "103") (name "Net-(D78-Do)") (class "Default")
      (node (ref "D78") (pin "1") (pinfunction "Do_1") (pintype "output"))
      (node (ref "D79") (pin "3") (pinfunction "Di_3") (pintype "input"))
    )
    (net (code "104") (name "Net-(D79-Do)") (class "Default")
      (node (ref "D79") (pin "1") (pinfunction "Do_1") (pintype "output"))
      (node (ref "D80") (pin "3") (pinfunction "Di_3") (pintype "input"))
    )
    (net (code "105") (name "Net-(D80-Do)") (class "Default")
      (node (ref "D80") (pin "1") (pinfunction "Do_1") (pintype "output"))
      (node (ref "D81") (pin "3") (pinfunction "Di_3") (pintype "input"))
    )
    (net (code "106") (name "Net-(D81-Do)") (class "Default")
      (node (ref "D81") (pin "1") (pinfunction "Do_1") (pintype "output"))
      (node (ref "D82") (pin "3") (pinfunction "Di_3") (pintype "input"))
    )
    (net (code "107") (name "Net-(D82-Do)") (class "Default")
      (node (ref "D82") (pin "1") (pinfunction "Do_1") (pintype "output"))
      (node (ref "D83") (pin "3") (pinfunction "Di_3") (pintype "input"))
    )
    (net (code "108") (name "Net-(D83-Do)") (class "Default")
      (node (ref "D83") (pin "1") (pinfunction "Do_1") (pintype "output"))
      (node (ref "D84") (pin "3") (pinfunction "Di_3") (pintype "input"))
    )
    (net (code "109") (name "Net-(D84-Do)") (class "Default")
      (node (ref "D84") (pin "1") (pinfunction "Do_1") (pintype "output"))
      (node (ref "D85") (pin "3") (pinfunction "Di_3") (pintype "input"))
    )
    (net (code "110") (name "Net-(D85-Do)") (class "Default")
      (node (ref "D85") (pin "1") (pinfunction "Do_1") (pintype "output"))
      (node (ref "D86") (pin "3") (pinfunction "Di_3") (pintype "input"))
    )
    (net (code "111") (name "Net-(D86-Do)") (class "Default")
      (node (ref "D86") (pin "1") (pinfunction "Do_1") (pintype "output"))
      (node (ref "D87") (pin "3") (pinfunction "Di_3") (pintype "input"))
    )
    (net (code "112") (name "Net-(D87-Do)") (class "Default")
      (node (ref "D87") (pin "1") (pinfunction "Do_1") (pintype "output"))
      (node (ref "D88") (pin "3") (pinfunction "Di_3") (pintype "input"))
    )
    (net (code "113") (name "Net-(D88-Do)") (class "Default")
      (node (ref "D88") (pin "1") (pinfunction "Do_1") (pintype "output"))
      (node (ref "D89") (pin "3") (pinfunction "Di_3") (pintype "input"))
    )
    (net (code "114") (name "Net-(D89-Do)") (class "Default")
      (node (ref "D89") (pin "1") (pinfunction "Do_1") (pintype "output"))
      (node (ref "D90") (pin "3") (pinfunction "Di_3") (pintype "input"))
    )
    (net (code "115") (name "Net-(D90-Do)") (class "Default")
      (node (ref "D90") (pin "1") (pinfunction "Do_1") (pintype "output"))
      (node (ref "D91") (pin "3") (pinfunction "Di_3") (pintype "input"))
    )
    (net (code "116") (name "Net-(D91-Do)") (class "Default")
      (node (ref "D91") (pin "1") (pinfunction "Do_1") (pintype "output"))
      (node (ref "D92") (pin "3") (pinfunction "Di_3") (pintype "input"))
    )
    (net (code "117") (name "Net-(D92-Do)") (class "Default")
      (node (ref "D92") (pin "1") (pinfunction "Do_1") (pintype "output"))
      (node (ref "D93") (pin "3") (pinfunction "Di_3") (pintype "input"))
    )
    (net (code "118") (name "Net-(D93-Do)") (class "Default")
      (node (ref "D93") (pin "1") (pinfunction "Do_1") (pintype "output"))
      (node (ref "D94") (pin "3") (pinfunction "Di_3") (pintype "input"))
    )
    (net (code "119") (name "Net-(D94-Do)") (class "Default")
      (node (ref "D94") (pin "1") (pinfunction "Do_1") (pintype "output"))
      (node (ref "D95") (pin "3") (pinfunction "Di_3") (pintype "input"))
    )
    (net (code "120") (name "Net-(D95-Do)") (class "Default")
      (node (ref "D95") (pin "1") (pinfunction "Do_1") (pintype "output"))
      (node (ref "D96") (pin "3") (pinfunction "Di_3") (pintype "input"))
    )
    (net (code "121") (name "Net-(D96-Do)") (class "Default")
      (node (ref "D96") (pin "1") (pinfunction "Do_1") (pintype "output"))
      (node (ref "D97") (pin "3") (pinfunction "Di_3") (pintype "input"))
    )
    (net (code "122") (name "Net-(D97-Do)") (class "Default")
      (node (ref "D97") (pin "1") (pinfunction "Do_1") (pintype "output"))
      (node (ref "D98") (pin "3") (pinfunction "Di_3") (pintype "input"))
    )
    (net (code "123") (name "Net-(D98-Do)") (class "Default")
      (node (ref "D98") (pin "1") (pinfunction "Do_1") (pintype "output"))
      (node (ref "D99") (pin "3") (pinfunction "Di_3") (pintype "input"))
    )
    (net (code "124") (name "Net-(D100-Di)") (class "Default")
      (node (ref "D100") (pin "3") (pinfunction "Di_3") (pintype "input"))
      (node (ref "D99") (pin "1") (pinfunction "Do_1") (pintype "output"))
    )
    (net (code "125") (name "Net-(D100-Do)") (class "Default")
      (node (ref "D100") (pin "1") (pinfunction "Do_1") (pintype "output"))
      (node (ref "D101") (pin "3") (pinfunction "Di_3") (pintype "input"))
    )
    (net (code "126") (name "Net-(D101-Do)") (class "Default")
      (node (ref "D101") (pin "1") (pinfunction "Do_1") (pintype "output"))
      (node (ref "D102") (pin "3") (pinfunction "Di_3") (pintype "input"))
    )
    (net (code "127") (name "Net-(D102-Do)") (class "Default")
      (node (ref "D102") (pin "1") (pinfunction "Do_1") (pintype "output"))
      (node (ref "D103") (pin "3") (pinfunction "Di_3") (pintype "input"))
    )
    (net (code "128") (name "Net-(D103-Do)") (class "Default")
      (node (ref "D103") (pin "1") (pinfunction "Do_1") (pintype "output"))
      (node (ref "D104") (pin "3") (pinfunction "Di_3") (pintype "input"))
    )
    (net (code "129") (name "Net-(D104-Do)") (class "Default")
      (node (ref "D104") (pin "1") (pinfunction "Do_1") (pintype "output"))
      (node (ref "D105") (pin "3") (pinfunction "Di_3") (pintype "input"))
    )
    (net (code "130") (name "Net-(D105-Do)") (class "Default")
      (node (ref "D105") (pin "1") (pinfunction "Do_1") (pintype "output"))
      (node (ref "D106") (pin "3") (pinfunction "Di_3") (pintype "input"))
    )
    (net (code "131") (name "Net-(D106-Do)") (class "Default")
      (node (ref "D106") (pin "1") (pinfunction "Do_1") (pintype "output"))
      (node (ref "D107") (pin "3") (pinfunction "Di_3") (pintype "input"))
    )
    (net (code "132") (name "Net-(D107-Do)") (class "Default")
      (node (ref "D107") (pin "1") (pinfunction "Do_1") (pintype "output"))
      (node (ref "D108") (pin "3") (pinfunction "Di_3") (pintype "input"))
    )
    (net (code "133") (name "Net-(D108-Do)") (class "Default")
      (node (ref "D108") (pin "1") (pinfunction "Do_1") (pintype "output"))
      (node (ref "D109") (pin "3") (pinfunction "Di_3") (pintype "input"))
    )
    (net (code "134") (name "Net-(D109-Do)") (class "Default")
      (node (ref "D109") (pin "1") (pinfunction "Do_1") (pintype "output"))
      (node (ref "D110") (pin "3") (pinfunction "Di_3") (pintype "input"))
    )
    (net (code "135") (name "Net-(D110-Do)") (class "Default")
      (node (ref "D110") (pin "1") (pinfunction "Do_1") (pintype "output"))
      (node (ref "D111") (pin "3") (pinfunction "Di_3") (pintype "input"))
    )
    (net (code "136") (name "Net-(D111-Do)") (class "Default")
      (node (ref "D111") (pin "1") (pinfunction "Do_1") (pintype "output"))
      (node (ref "D112") (pin "3") (pinfunction "Di_3") (pintype "input"))
    )
    (net (code "137") (name "Net-(D112-Do)") (class "Default")
      (node (ref "D112") (pin "1") (pinfunction "Do_1") (pintype "output"))
      (node (ref "D113") (pin "3") (pinfunction "Di_3") (pintype "input"))
    )
    (net (code "138") (name "Net-(D113-Do)") (class "Default")
      (node (ref "D113") (pin "1") (pinfunction "Do_1") (pintype "output"))
      (node (ref "D114") (pin "3") (pinfunction "Di_3") (pintype "input"))
    )
    (net (code "139") (name "Net-(D114-Do)") (class "Default")
      (node (ref "D114") (pin "1") (pinfunction "Do_1") (pintype "output"))
      (node (ref "D115") (pin "3") (pinfunction "Di_3") (pintype "input"))
    )
    (net (code "140") (name "Net-(D115-Do)") (class "Default")
      (node (ref "D115") (pin "1") (pinfunction "Do_1") (pintype "output"))
      (node (ref "D116") (pin "3") (pinfunction "Di_3") (pintype "input"))
    )
    (net (code "141") (name "Net-(D116-Do)") (class "Default")
      (node (ref "D116") (pin "1") (pinfunction "Do_1") (pintype "output"))
      (node (ref "D117") (pin "3") (pinfunction "Di_3") (pintype "input"))
    )
    (net (code "142") (name "Net-(D117-Do)") (class "Default")
      (node (ref "D117") (pin "1") (pinfunction "Do_1") (pintype "output"))
      (node (ref "D118") (pin "3") (pinfunction "Di_3") (pintype "input"))
    )
    (net (code "143") (name "Net-(D118-Do)") (class "Default")
      (node (ref "D118") (pin "1") (pinfunction "Do_1") (pintype "output"))
      (node (ref "D119") (pin "3") (pinfunction "Di_3") (pintype "input"))
    )
    (net (code "144") (name "Net-(D119-Do)") (class "Default")
      (node (ref "D119") (pin "1") (pinfunction "Do_1") (pintype "output"))
      (node (ref "D120") (pin "3") (pinfunction "Di_3") (pintype "input"))
    )
    (net (code "145") (name "Net-(D120-Do)") (class "Default")
      (node (ref "D120") (pin "1") (pinfunction "Do_1") (pintype "output"))
      (node (ref "D121") (pin "3") (pinfunction "Di_3") (pintype "input"))
    )
    (net (code "146") (name "Net-(D121-Do)") (class "Default")
      (node (ref "D121") (pin "1") (pinfunction "Do_1") (pintype "output"))
      (node (ref "D122") (pin "3") (pinfunction "Di_3") (pintype "input"))
    )
    (net (code "147") (name "Net-(D122-Do)") (class "Default")
      (node (ref "D122") (pin "1") (pinfunction "Do_1") (pintype "output"))
      (node (ref "D123") (pin "3") (pinfunction "Di_3") (pintype "input"))
    )
    (net (code "148") (name "Net-(D123-Do)") (class "Default")
      (node (ref "D123") (pin "1") (pinfunction "Do_1") (pintype "output"))
      (node (ref "D124") (pin "3") (pinfunction "Di_3") (pintype "input"))
    )
    (net (code "149") (name "Net-(D124-Do)") (class "Default")
      (node (ref "D124") (pin "1") (pinfunction "Do_1") (pintype "output"))
      (node (ref "D125") (pin "3") (pinfunction "Di_3") (pintype "input"))
    )
    (net (code "150") (name "Net-(D125-Do)") (class "Default")
      (node (ref "D125") (pin "1") (pinfunction "Do_1") (pintype "output"))
      (node (ref "D126") (pin "3") (pinfunction "Di_3") (pintype "input"))
    )
    (net (code "151") (name "Net-(D126-Do)") (class "Default")
      (node (ref "D126") (pin "1") (pinfunction "Do_1") (pintype "output"))
      (node (ref "D127") (pin "3") (pinfunction "Di_3") (pintype "input"))
    )
    (net (code "152") (name "Net-(D127-Do)") (class "Default")
      (node (ref "D127") (pin "1") (pinfunction "Do_1") (pintype "output"))
      (node (ref "D128") (pin "3") (pinfunction "Di_3") (pintype "input"))
    )
    (net (code "153") (name "Net-(R1-Pad2)") (class "Default")
      (node (ref "R1") (pin "2") (pinfunction "2_2") (pintype "passive"))
      (node (ref "SW1") (pin "1") (pinfunction "1_1") (pintype "passive"))
    )
    (net (code "154") (name "VUSB") (class "Default")
      (node (ref "C1") (pin "1") (pinfunction "1_1") (pintype "passive"))
      (node (ref "C10") (pin "1") (pinfunction "1_1") (pintype "passive"))
      (node (ref "C11") (pin "1") (pinfunction "1_1") (pintype "passive"))
      (node (ref "C12") (pin "1") (pinfunction "1_1") (pintype "passive"))
      (node (ref "C13") (pin "1") (pinfunction "1_1") (pintype "passive"))
      (node (ref "C14") (pin "1") (pinfunction "1_1") (pintype "passive"))
      (node (ref "C15") (pin "1") (pinfunction "1_1") (pintype "passive"))
      (node (ref "C16") (pin "1") (pinfunction "1_1") (pintype "passive"))
      (node (ref "C17") (pin "1") (pinfunction "1_1") (pintype "passive"))
      (node (ref "C18") (pin "1") (pinfunction "1_1") (pintype "passive"))
      (node (ref "C19") (pin "1") (pinfunction "1_1") (pintype "passive"))
      (node (ref "C2") (pin "1") (pinfunction "1_1") (pintype "passive"))
      (node (ref "C20") (pin "1") (pinfunction "1_1") (pintype "passive"))
      (node (ref "C21") (pin "1") (pinfunction "1_1") (pintype "passive"))
      (node (ref "C22") (pin "1") (pinfunction "1_1") (pintype "passive"))
      (node (ref "C23") (pin "1") (pinfunction "1_1") (pintype "passive"))
      (node (ref "C24") (pin "1") (pinfunction "1_1") (pintype "passive"))
      (node (ref "C25") (pin "1") (pinfunction "1_1") (pintype "passive"))
      (node (ref "C26") (pin "1") (pinfunction "1_1") (pintype "passive"))
      (node (ref "C27") (pin "1") (pinfunction "1_1") (pintype "passive"))
      (node (ref "C28") (pin "1") (pinfunction "1_1") (pintype "passive"))
      (node (ref "C29") (pin "1") (pinfunction "1_1") (pintype "passive"))
      (node (ref "C3") (pin "1") (pinfunction "1_1") (pintype "passive"))
      (node (ref "C30") (pin "1") (pinfunction "1_1") (pintype "passive"))
      (node (ref "C31") (pin "1") (pinfunction "1_1") (pintype "passive"))
      (node (ref "C32") (pin "1") (pinfunction "1_1") (pintype "passive"))
      (node (ref "C33") (pin "1") (pinfunction "1_1") (pintype "passive"))
      (node (ref "C34") (pin "1") (pinfunction "1_1") (pintype "passive"))
      (node (ref "C35") (pin "1") (pinfunction "1_1") (pintype "passive"))
      (node (ref "C36") (pin "1") (pinfunction "1_1") (pintype "passive"))
      (node (ref "C37") (pin "1") (pinfunction "1_1") (pintype "passive"))
      (node (ref "C38") (pin "1") (pinfunction "1_1") (pintype "passive"))
      (node (ref "C39") (pin "1") (pinfunction "1_1") (pintype "passive"))
      (node (ref "C4") (pin "1") (pinfunction "1_1") (pintype "passive"))
      (node (ref "C40") (pin "1") (pinfunction "1_1") (pintype "passive"))
      (node (ref "C41") (pin "1") (pinfunction "1_1") (pintype "passive"))
      (node (ref "C42") (pin "1") (pinfunction "1_1") (pintype "passive"))
      (node (ref "C43") (pin "1") (pinfunction "1_1") (pintype "passive"))
      (node (ref "C44") (pin "1") (pinfunction "1_1") (pintype "passive"))
      (node (ref "C45") (pin "1") (pinfunction "1_1") (pintype "passive"))
      (node (ref "C46") (pin "1") (pinfunction "1_1") (pintype "passive"))
      (node (ref "C47") (pin "1") (pinfunction "1_1") (pintype "passive"))
      (node (ref "C48") (pin "1") (pinfunction "1_1") (pintype "passive"))
      (node (ref "C49") (pin "1") (pinfunction "1_1") (pintype "passive"))
      (node (ref "C5") (pin "1") (pinfunction "1_1") (pintype "passive"))
      (node (ref "C50") (pin "1") (pinfunction "1_1") (pintype "passive"))
      (node (ref "C51") (pin "1") (pinfunction "1_1") (pintype "passive"))
      (node (ref "C52") (pin "1") (pinfunction "1_1") (pintype "passive"))
      (node (ref "C53") (pin "1") (pinfunction "1_1") (pintype "passive"))
      (node (ref "C54") (pin "1") (pinfunction "1_1") (pintype "passive"))
      (node (ref "C55") (pin "1") (pinfunction "1_1") (pintype "passive"))
      (node (ref "C56") (pin "1") (pinfunction "1_1") (pintype "passive"))
      (node (ref "C57") (pin "1") (pinfunction "1_1") (pintype "passive"))
      (node (ref "C58") (pin "1") (pinfunction "1_1") (pintype "passive"))
      (node (ref "C59") (pin "1") (pinfunction "1_1") (pintype "passive"))
      (node (ref "C6") (pin "1") (pinfunction "1_1") (pintype "passive"))
      (node (ref "C60") (pin "1") (pinfunction "1_1") (pintype "passive"))
      (node (ref "C61") (pin "1") (pinfunction "1_1") (pintype "passive"))
      (node (ref "C62") (pin "1") (pinfunction "1_1") (pintype "passive"))
      (node (ref "C63") (pin "1") (pinfunction "1_1") (pintype "passive"))
      (node (ref "C64") (pin "1") (pinfunction "1_1") (pintype "passive"))
      (node (ref "C65") (pin "1") (pinfunction "1_1") (pintype "passive"))
      (node (ref "C66") (pin "1") (pinfunction "1_1") (pintype "passive"))
      (node (ref "C7") (pin "1") (pinfunction "1_1") (pintype "passive"))
      (node (ref "C8") (pin "1") (pinfunction "1_1") (pintype "passive"))
      (node (ref "C9") (pin "1") (pinfunction "1_1") (pintype "passive"))
      (node (ref "D1") (pin "4") (pinfunction "V+_4") (pintype "power_in"))
      (node (ref "D100") (pin "4") (pinfunction "V+_4") (pintype "power_in"))
      (node (ref "D101") (pin "4") (pinfunction "V+_4") (pintype "power_in"))
      (node (ref "D102") (pin "4") (pinfunction "V+_4") (pintype "power_in"))
      (node (ref "D103") (pin "4") (pinfunction "V+_4") (pintype "power_in"))
      (node (ref "D104") (pin "4") (pinfunction "V+_4") (pintype "power_in"))
      (node (ref "D105") (pin "4") (pinfunction "V+_4") (pintype "power_in"))
      (node (ref "D106") (pin "4") (pinfunction "V+_4") (pintype "power_in"))
      (node (ref "D107") (pin "4") (pinfunction "V+_4") (pintype "power_in"))
      (node (ref "D108") (pin "4") (pinfunction "V+_4") (pintype "power_in"))
      (node (ref "D109") (pin "4") (pinfunction "V+_4") (pintype "power_in"))
      (node (ref "D110") (pin "4") (pinfunction "V+_4") (pintype "power_in"))
      (node (ref "D111") (pin "4") (pinfunction "V+_4") (pintype "power_in"))
      (node (ref "D112") (pin "4") (pinfunction "V+_4") (pintype "power_in"))
      (node (ref "D113") (pin "4") (pinfunction "V+_4") (pintype "power_in"))
      (node (ref "D114") (pin "4") (pinfunction "V+_4") (pintype "power_in"))
      (node (ref "D115") (pin "4") (pinfunction "V+_4") (pintype "power_in"))
      (node (ref "D116") (pin "4") (pinfunction "V+_4") (pintype "power_in"))
      (node (ref "D117") (pin "4") (pinfunction "V+_4") (pintype "power_in"))
      (node (ref "D118") (pin "4") (pinfunction "V+_4") (pintype "power_in"))
      (node (ref "D119") (pin "4") (pinfunction "V+_4") (pintype "power_in"))
      (node (ref "D120") (pin "4") (pinfunction "V+_4") (pintype "power_in"))
      (node (ref "D121") (pin "4") (pinfunction "V+_4") (pintype "power_in"))
      (node (ref "D122") (pin "4") (pinfunction "V+_4") (pintype "power_in"))
      (node (ref "D123") (pin "4") (pinfunction "V+_4") (pintype "power_in"))
      (node (ref "D124") (pin "4") (pinfunction "V+_4") (pintype "power_in"))
      (node (ref "D125") (pin "4") (pinfunction "V+_4") (pintype "power_in"))
      (node (ref "D126") (pin "4") (pinfunction "V+_4") (pintype "power_in"))
      (node (ref "D127") (pin "4") (pinfunction "V+_4") (pintype "power_in"))
      (node (ref "D128") (pin "4") (pinfunction "V+_4") (pintype "power_in"))
      (node (ref "D2") (pin "4") (pinfunction "V+_4") (pintype "power_in"))
      (node (ref "D3") (pin "4") (pinfunction "V+_4") (pintype "power_in"))
      (node (ref "D4") (pin "4") (pinfunction "V+_4") (pintype "power_in"))
      (node (ref "D69") (pin "4") (pinfunction "V+_4") (pintype "power_in"))
      (node (ref "D70") (pin "4") (pinfunction "V+_4") (pintype "power_in"))
      (node (ref "D71") (pin "4") (pinfunction "V+_4") (pintype "power_in"))
      (node (ref "D72") (pin "4") (pinfunction "V+_4") (pintype "power_in"))
      (node (ref "D73") (pin "4") (pinfunction "V+_4") (pintype "power_in"))
      (node (ref "D74") (pin "4") (pinfunction "V+_4") (pintype "power_in"))
      (node (ref "D75") (pin "4") (pinfunction "V+_4") (pintype "power_in"))
      (node (ref "D76") (pin "4") (pinfunction "V+_4") (pintype "power_in"))
      (node (ref "D77") (pin "4") (pinfunction "V+_4") (pintype "power_in"))
      (node (ref "D78") (pin "4") (pinfunction "V+_4") (pintype "power_in"))
      (node (ref "D79") (pin "4") (pinfunction "V+_4") (pintype "power_in"))
      (node (ref "D80") (pin "4") (pinfunction "V+_4") (pintype "power_in"))
      (node (ref "D81") (pin "4") (pinfunction "V+_4") (pintype "power_in"))
      (node (ref "D82") (pin "4") (pinfunction "V+_4") (pintype "power_in"))
      (node (ref "D83") (pin "4") (pinfunction "V+_4") (pintype "power_in"))
      (node (ref "D84") (pin "4") (pinfunction "V+_4") (pintype "power_in"))
      (node (ref "D85") (pin "4") (pinfunction "V+_4") (pintype "power_in"))
      (node (ref "D86") (pin "4") (pinfunction "V+_4") (pintype "power_in"))
      (node (ref "D87") (pin "4") (pinfunction "V+_4") (pintype "power_in"))
      (node (ref "D88") (pin "4") (pinfunction "V+_4") (pintype "power_in"))
      (node (ref "D89") (pin "4") (pinfunction "V+_4") (pintype "power_in"))
      (node (ref "D90") (pin "4") (pinfunction "V+_4") (pintype "power_in"))
      (node (ref "D91") (pin "4") (pinfunction "V+_4") (pintype "power_in"))
      (node (ref "D92") (pin "4") (pinfunction "V+_4") (pintype "power_in"))
      (node (ref "D93") (pin "4") (pinfunction "V+_4") (pintype "power_in"))
      (node (ref "D94") (pin "4") (pinfunction "V+_4") (pintype "power_in"))
      (node (ref "D95") (pin "4") (pinfunction "V+_4") (pintype "power_in"))
      (node (ref "D96") (pin "4") (pinfunction "V+_4") (pintype "power_in"))
      (node (ref "D97") (pin "4") (pinfunction "V+_4") (pintype "power_in"))
      (node (ref "D98") (pin "4") (pinfunction "V+_4") (pintype "power_in"))
      (node (ref "D99") (pin "4") (pinfunction "V+_4") (pintype "power_in"))
      (node (ref "J1") (pin "A4") (pinfunction "VBUS_A4") (pintype "passive"))
      (node (ref "J1") (pin "A9") (pinfunction "VBUS_A9") (pintype "passive"))
      (node (ref "J1") (pin "B4") (pinfunction "VBUS_B4") (pintype "passive"))
      (node (ref "J1") (pin "B9") (pinfunction "VBUS_B9") (pintype "passive"))
      (node (ref "P2") (pin "2") (pinfunction "2_2") (pintype "passive"))
      (node (ref "R1") (pin "1") (pinfunction "1_1") (pintype "passive"))
      (node (ref "U1") (pin "2") (pinfunction "VDD_2") (pintype "power_in"))
    )
    (net (code "155") (name "unconnected-(J1-SBU1-PadA8)") (class "Default")
      (node (ref "J1") (pin "A8") (pinfunction "SBU1_A8") (pintype "passive+no_connect"))
    )
    (net (code "156") (name "unconnected-(J1-SBU2-PadB8)") (class "Default")
      (node (ref "J1") (pin "B8") (pinfunction "SBU2_B8") (pintype "passive+no_connect"))
    )
    (net (code "157") (name "unconnected-(U1-PA6{slash}MISO-Pad11)") (class "Default")
      (node (ref "U1") (pin "11") (pinfunction "PA6/MISO_11") (pintype "bidirectional"))
    )
    (net (code "158") (name "unconnected-(U1-PB0-Pad13)") (class "Default")
      (node (ref "U1") (pin "13") (pinfunction "PB0_13") (pintype "bidirectional"))
    )
    (net (code "159") (name "unconnected-(U1-PB3-Pad14)") (class "Default")
      (node (ref "U1") (pin "14") (pinfunction "PB3_14") (pintype "bidirectional"))
    )
    (net (code "160") (name "unconnected-(U1-PB4-Pad15)") (class "Default")
      (node (ref "U1") (pin "15") (pinfunction "PB4_15") (pintype "bidirectional"))
    )
    (net (code "161") (name "unconnected-(U1-PC14{slash}CC1-Pad28)") (class "Default")
      (node (ref "U1") (pin "28") (pinfunction "PC14/CC1_28") (pintype "bidirectional"))
    )
    (net (code "162") (name "unconnected-(U1-PC15{slash}CC2-Pad1)") (class "Default")
      (node (ref "U1") (pin "1") (pinfunction "PC15/CC2_1") (pintype "bidirectional"))
    )
  )
)
